# c421.net
KiCad netlist of a schematic drawn in EAGLE
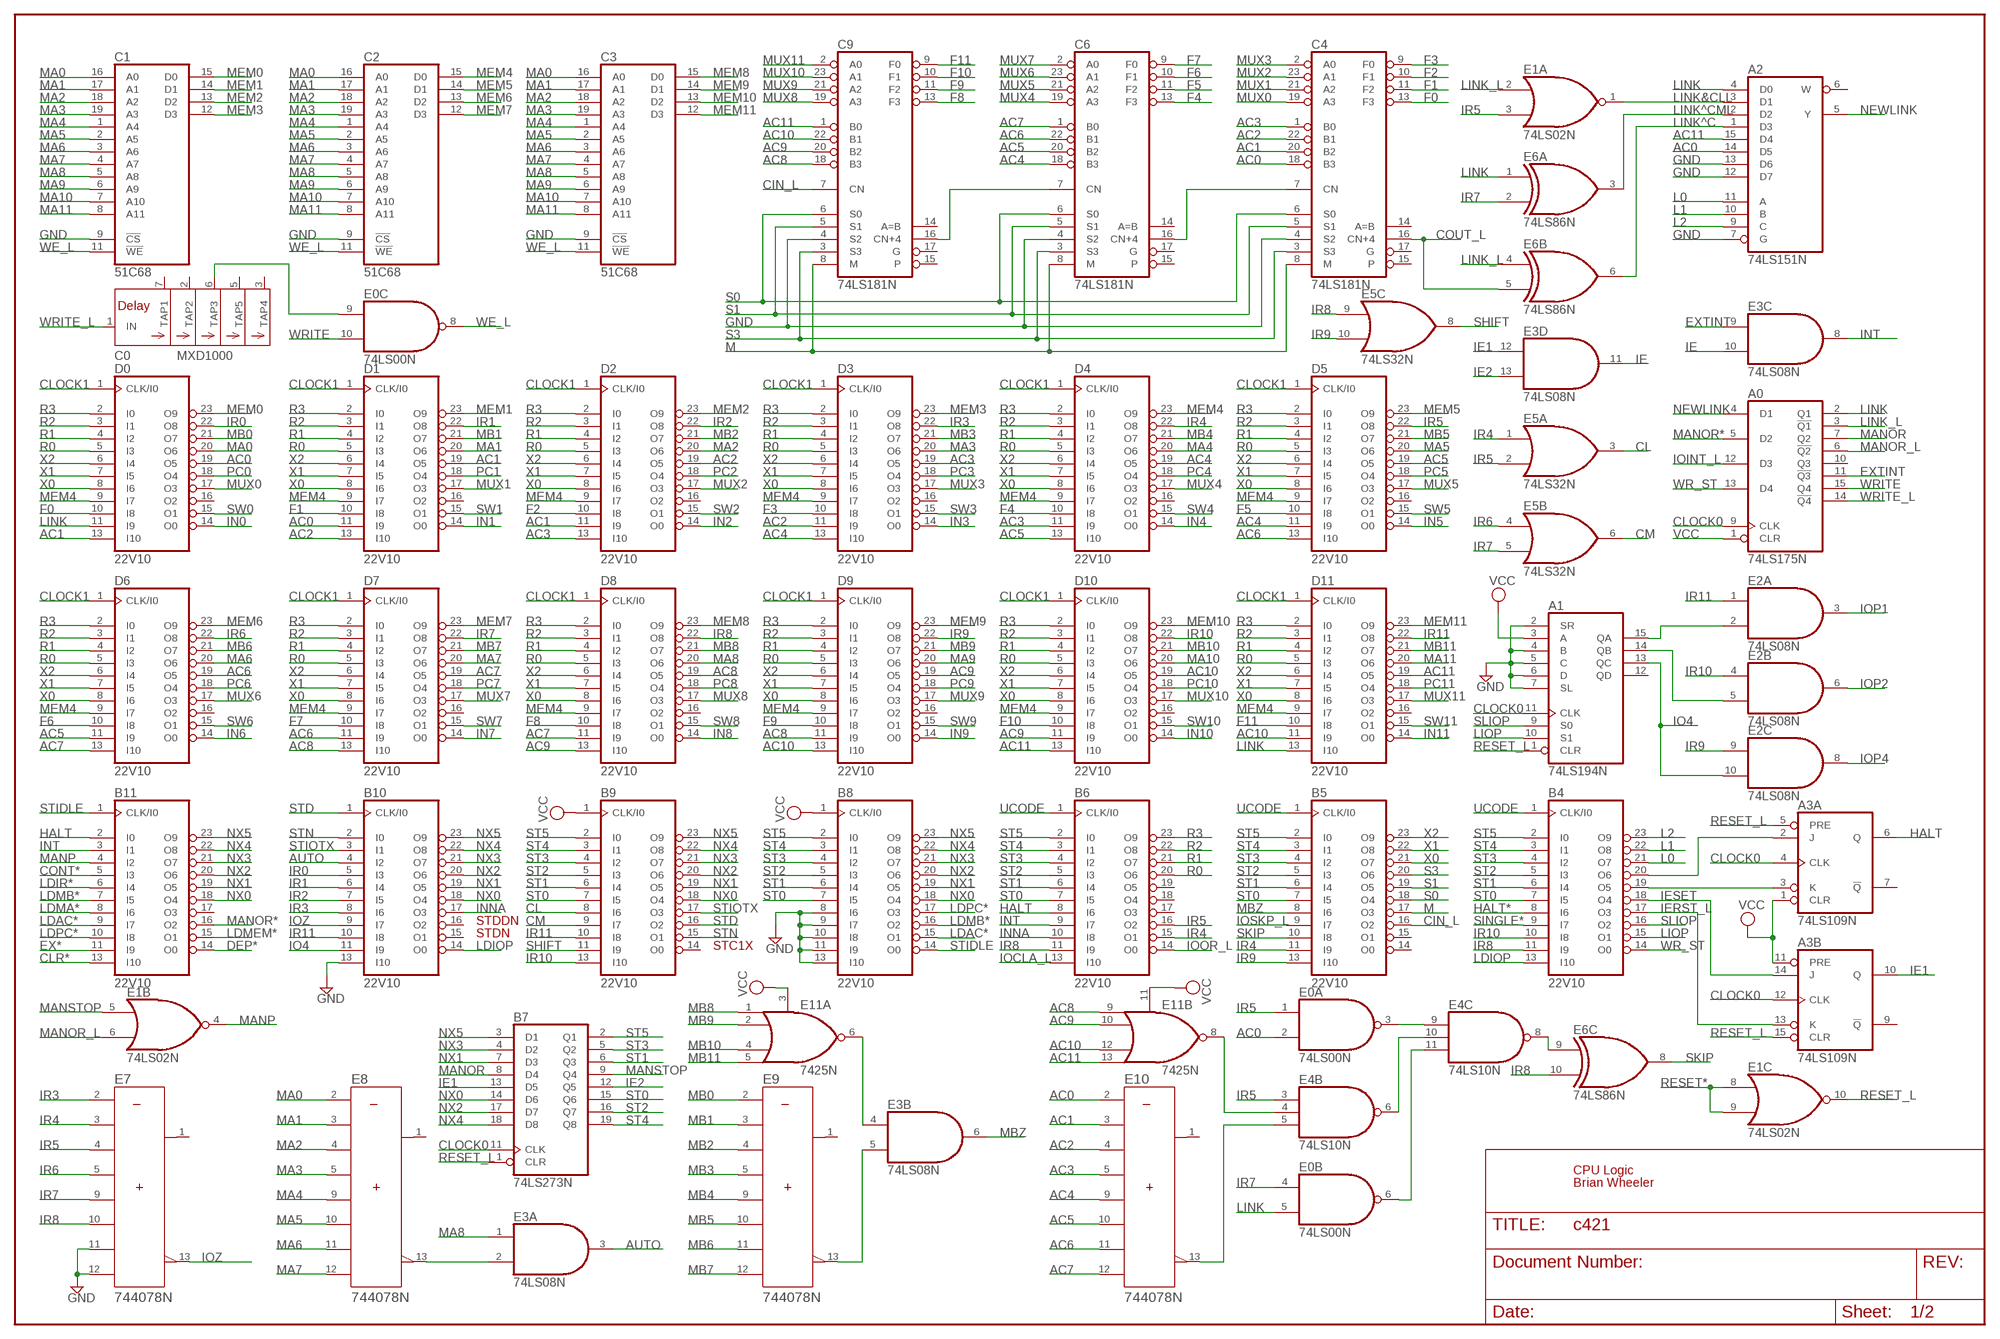
[diagram p0: schematic, sheet 1]
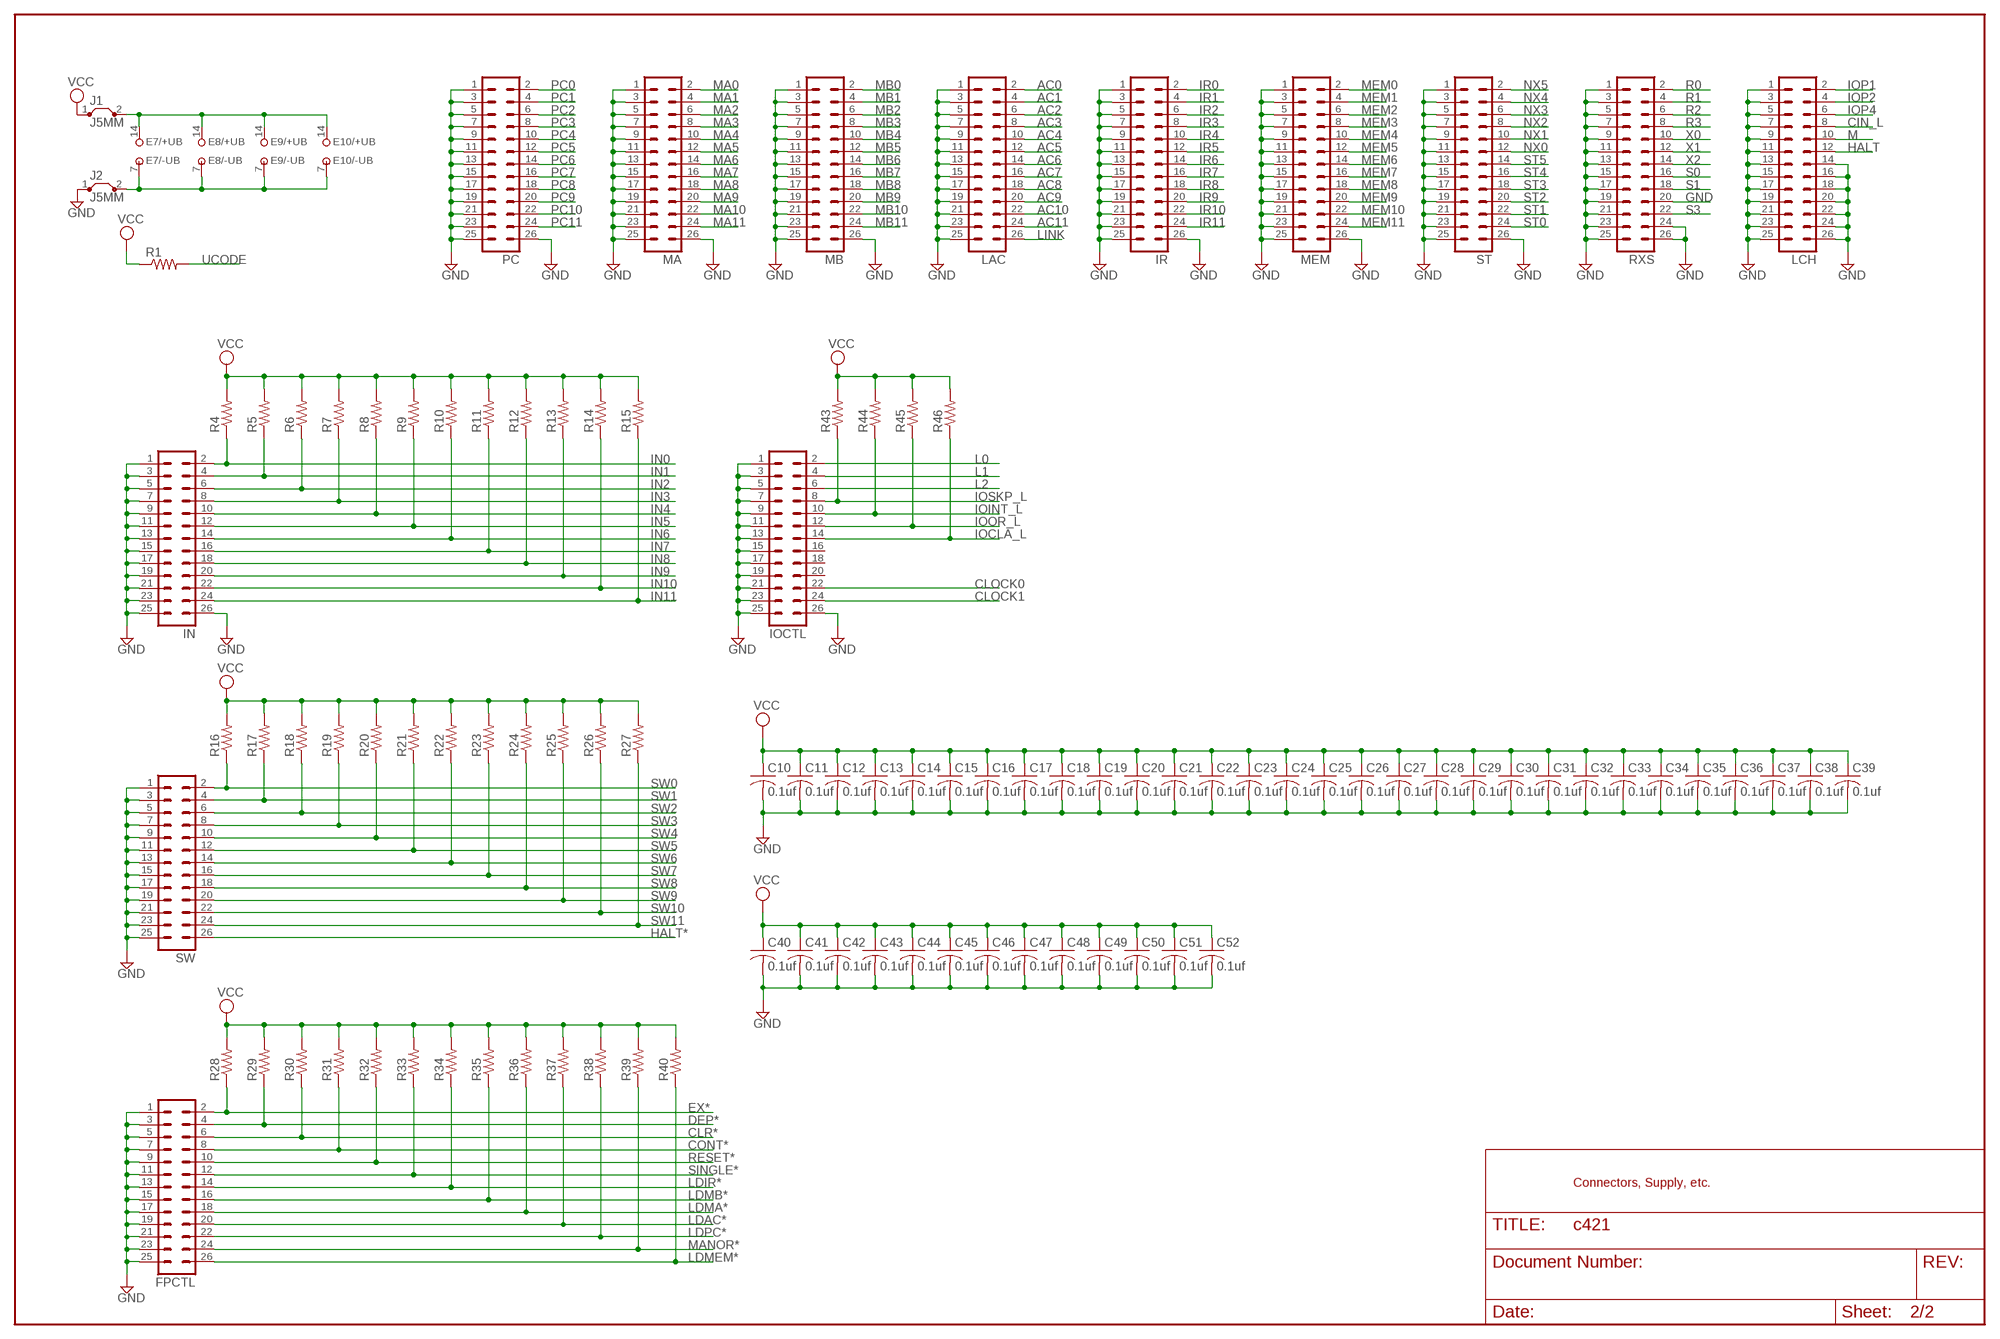
[diagram p1: schematic, sheet 2]

(export (version "E")
  (design (tool "Eeschema 10.0.6"))
  (components
    (comp (ref "A0")
      (value "74LS175N")
      (footprint "eagle-import:DIL16")
      (libsource (lib "eagle-import") (part "74175NLS"))
    )
    (comp (ref "A1")
      (value "74LS194N")
      (footprint "eagle-import:DIL16")
      (libsource (lib "eagle-import") (part "74194NS"))
    )
    (comp (ref "A2")
      (value "74LS151N")
      (footprint "eagle-import:DIL16")
      (libsource (lib "eagle-import") (part "74151NLS"))
    )
    (comp (ref "A3")
      (value "74LS109N")
      (footprint "eagle-import:DIL16")
      (libsource (lib "eagle-import") (part "74109NLS"))
    )
    (comp (ref "B4")
      (value "22V10")
      (footprint "eagle-import:DIL24-3")
      (fields (field (name "MPN") "GAL22V10D-7LPN"))
      (libsource (lib "eagle-import") (part "22V10"))
    )
    (comp (ref "B5")
      (value "22V10")
      (footprint "eagle-import:DIL24-3")
      (fields (field (name "MPN") "GAL22V10D-7LPN"))
      (libsource (lib "eagle-import") (part "22V10"))
    )
    (comp (ref "B6")
      (value "22V10")
      (footprint "eagle-import:DIL24-3")
      (fields (field (name "MPN") "GAL22V10D-7LPN"))
      (libsource (lib "eagle-import") (part "22V10"))
    )
    (comp (ref "B7")
      (value "74LS273N")
      (footprint "eagle-import:DIL20")
      (libsource (lib "eagle-import") (part "74273N"))
    )
    (comp (ref "B8")
      (value "22V10")
      (footprint "eagle-import:DIL24-3")
      (fields (field (name "MPN") "GAL22V10D-7LPN"))
      (libsource (lib "eagle-import") (part "22V10"))
    )
    (comp (ref "B9")
      (value "22V10")
      (footprint "eagle-import:DIL24-3")
      (fields (field (name "MPN") "GAL22V10D-7LPN"))
      (libsource (lib "eagle-import") (part "22V10"))
    )
    (comp (ref "B10")
      (value "22V10")
      (footprint "eagle-import:DIL24-3")
      (fields (field (name "MPN") "GAL22V10D-7LPN"))
      (libsource (lib "eagle-import") (part "22V10"))
    )
    (comp (ref "B11")
      (value "22V10")
      (footprint "eagle-import:DIL24-3")
      (fields (field (name "MPN") "GAL22V10D-7LPN"))
      (libsource (lib "eagle-import") (part "22V10"))
    )
    (comp (ref "C0")
      (value "MXD1000")
      (footprint "eagle-import:DIL08")
      (libsource (lib "eagle-import") (part "MXD1000"))
    )
    (comp (ref "C1")
      (value "51C68")
      (footprint "eagle-import:DIL20")
      (libsource (lib "eagle-import") (part "51C68"))
    )
    (comp (ref "C2")
      (value "51C68")
      (footprint "eagle-import:DIL20")
      (libsource (lib "eagle-import") (part "51C68"))
    )
    (comp (ref "C3")
      (value "51C68")
      (footprint "eagle-import:DIL20")
      (libsource (lib "eagle-import") (part "51C68"))
    )
    (comp (ref "C4")
      (value "74LS181N")
      (footprint "eagle-import:DIL24-6")
      (libsource (lib "eagle-import") (part "74181NLS"))
    )
    (comp (ref "C6")
      (value "74LS181N")
      (footprint "eagle-import:DIL24-6")
      (libsource (lib "eagle-import") (part "74181NLS"))
    )
    (comp (ref "C9")
      (value "74LS181N")
      (footprint "eagle-import:DIL24-6")
      (libsource (lib "eagle-import") (part "74181NLS"))
    )
    (comp (ref "D0")
      (value "22V10")
      (footprint "eagle-import:DIL24-3")
      (fields (field (name "MPN") "GAL22V10D-7LPN"))
      (libsource (lib "eagle-import") (part "22V10"))
    )
    (comp (ref "D1")
      (value "22V10")
      (footprint "eagle-import:DIL24-3")
      (fields (field (name "MPN") "GAL22V10D-7LPN"))
      (libsource (lib "eagle-import") (part "22V10"))
    )
    (comp (ref "D2")
      (value "22V10")
      (footprint "eagle-import:DIL24-3")
      (fields (field (name "MPN") "GAL22V10D-7LPN"))
      (libsource (lib "eagle-import") (part "22V10"))
    )
    (comp (ref "D3")
      (value "22V10")
      (footprint "eagle-import:DIL24-3")
      (fields (field (name "MPN") "GAL22V10D-7LPN"))
      (libsource (lib "eagle-import") (part "22V10"))
    )
    (comp (ref "D4")
      (value "22V10")
      (footprint "eagle-import:DIL24-3")
      (fields (field (name "MPN") "GAL22V10D-7LPN"))
      (libsource (lib "eagle-import") (part "22V10"))
    )
    (comp (ref "D5")
      (value "22V10")
      (footprint "eagle-import:DIL24-3")
      (fields (field (name "MPN") "GAL22V10D-7LPN"))
      (libsource (lib "eagle-import") (part "22V10"))
    )
    (comp (ref "D6")
      (value "22V10")
      (footprint "eagle-import:DIL24-3")
      (fields (field (name "MPN") "GAL22V10D-7LPN"))
      (libsource (lib "eagle-import") (part "22V10"))
    )
    (comp (ref "D7")
      (value "22V10")
      (footprint "eagle-import:DIL24-3")
      (fields (field (name "MPN") "GAL22V10D-7LPN"))
      (libsource (lib "eagle-import") (part "22V10"))
    )
    (comp (ref "D8")
      (value "22V10")
      (footprint "eagle-import:DIL24-3")
      (fields (field (name "MPN") "GAL22V10D-7LPN"))
      (libsource (lib "eagle-import") (part "22V10"))
    )
    (comp (ref "D9")
      (value "22V10")
      (footprint "eagle-import:DIL24-3")
      (fields (field (name "MPN") "GAL22V10D-7LPN"))
      (libsource (lib "eagle-import") (part "22V10"))
    )
    (comp (ref "D10")
      (value "22V10")
      (footprint "eagle-import:DIL24-3")
      (fields (field (name "MPN") "GAL22V10D-7LPN"))
      (libsource (lib "eagle-import") (part "22V10"))
    )
    (comp (ref "D11")
      (value "22V10")
      (footprint "eagle-import:DIL24-3")
      (fields (field (name "MPN") "GAL22V10D-7LPN"))
      (libsource (lib "eagle-import") (part "22V10"))
    )
    (comp (ref "E0")
      (value "74LS00N")
      (footprint "eagle-import:DIL14")
      (libsource (lib "eagle-import") (part "7400NLS"))
    )
    (comp (ref "E1")
      (value "74LS02N")
      (footprint "eagle-import:DIL14")
      (libsource (lib "eagle-import") (part "7402NLS"))
    )
    (comp (ref "E2")
      (value "74LS08N")
      (footprint "eagle-import:DIL14")
      (libsource (lib "eagle-import") (part "7408NLS"))
    )
    (comp (ref "E3")
      (value "74LS08N")
      (footprint "eagle-import:DIL14")
      (libsource (lib "eagle-import") (part "7408NLS"))
    )
    (comp (ref "E4")
      (value "74LS10N")
      (footprint "eagle-import:DIL14")
      (libsource (lib "eagle-import") (part "7410NLS"))
    )
    (comp (ref "E5")
      (value "74LS32N")
      (footprint "eagle-import:DIL14")
      (libsource (lib "eagle-import") (part "7432NLS"))
    )
    (comp (ref "E6")
      (value "74LS86N")
      (footprint "eagle-import:DIL14")
      (libsource (lib "eagle-import") (part "7486NLS"))
    )
    (comp (ref "E7")
      (value "744078N")
      (footprint "eagle-import:DIL14")
      (libsource (lib "eagle-import") (part "744078N"))
    )
    (comp (ref "E8")
      (value "744078N")
      (footprint "eagle-import:DIL14")
      (libsource (lib "eagle-import") (part "744078N"))
    )
    (comp (ref "E9")
      (value "744078N")
      (footprint "eagle-import:DIL14")
      (libsource (lib "eagle-import") (part "744078N"))
    )
    (comp (ref "E10")
      (value "744078N")
      (footprint "eagle-import:DIL14")
      (libsource (lib "eagle-import") (part "744078N"))
    )
    (comp (ref "E11")
      (value "7425N")
      (footprint "eagle-import:DIL14")
      (libsource (lib "eagle-import") (part "7425N"))
    )
    (comp (ref "C10")
      (value "0.1uf")
      (footprint "eagle-import:C050-025X075")
      (libsource (lib "eagle-import") (part "C-US050-025X075"))
    )
    (comp (ref "C11")
      (value "0.1uf")
      (footprint "eagle-import:C050-025X075")
      (libsource (lib "eagle-import") (part "C-US050-025X075"))
    )
    (comp (ref "C12")
      (value "0.1uf")
      (footprint "eagle-import:C050-025X075")
      (libsource (lib "eagle-import") (part "C-US050-025X075"))
    )
    (comp (ref "C13")
      (value "0.1uf")
      (footprint "eagle-import:C050-025X075")
      (libsource (lib "eagle-import") (part "C-US050-025X075"))
    )
    (comp (ref "C14")
      (value "0.1uf")
      (footprint "eagle-import:C050-025X075")
      (libsource (lib "eagle-import") (part "C-US050-025X075"))
    )
    (comp (ref "C15")
      (value "0.1uf")
      (footprint "eagle-import:C050-025X075")
      (libsource (lib "eagle-import") (part "C-US050-025X075"))
    )
    (comp (ref "C16")
      (value "0.1uf")
      (footprint "eagle-import:C050-025X075")
      (libsource (lib "eagle-import") (part "C-US050-025X075"))
    )
    (comp (ref "C17")
      (value "0.1uf")
      (footprint "eagle-import:C050-025X075")
      (libsource (lib "eagle-import") (part "C-US050-025X075"))
    )
    (comp (ref "C18")
      (value "0.1uf")
      (footprint "eagle-import:C050-025X075")
      (libsource (lib "eagle-import") (part "C-US050-025X075"))
    )
    (comp (ref "C19")
      (value "0.1uf")
      (footprint "eagle-import:C050-025X075")
      (libsource (lib "eagle-import") (part "C-US050-025X075"))
    )
    (comp (ref "C20")
      (value "0.1uf")
      (footprint "eagle-import:C050-025X075")
      (libsource (lib "eagle-import") (part "C-US050-025X075"))
    )
    (comp (ref "C21")
      (value "0.1uf")
      (footprint "eagle-import:C050-025X075")
      (libsource (lib "eagle-import") (part "C-US050-025X075"))
    )
    (comp (ref "C22")
      (value "0.1uf")
      (footprint "eagle-import:C050-025X075")
      (libsource (lib "eagle-import") (part "C-US050-025X075"))
    )
    (comp (ref "C23")
      (value "0.1uf")
      (footprint "eagle-import:C050-025X075")
      (libsource (lib "eagle-import") (part "C-US050-025X075"))
    )
    (comp (ref "C24")
      (value "0.1uf")
      (footprint "eagle-import:C050-025X075")
      (libsource (lib "eagle-import") (part "C-US050-025X075"))
    )
    (comp (ref "C25")
      (value "0.1uf")
      (footprint "eagle-import:C050-025X075")
      (libsource (lib "eagle-import") (part "C-US050-025X075"))
    )
    (comp (ref "C26")
      (value "0.1uf")
      (footprint "eagle-import:C050-025X075")
      (libsource (lib "eagle-import") (part "C-US050-025X075"))
    )
    (comp (ref "C27")
      (value "0.1uf")
      (footprint "eagle-import:C050-025X075")
      (libsource (lib "eagle-import") (part "C-US050-025X075"))
    )
    (comp (ref "C28")
      (value "0.1uf")
      (footprint "eagle-import:C050-025X075")
      (libsource (lib "eagle-import") (part "C-US050-025X075"))
    )
    (comp (ref "C29")
      (value "0.1uf")
      (footprint "eagle-import:C050-025X075")
      (libsource (lib "eagle-import") (part "C-US050-025X075"))
    )
    (comp (ref "C30")
      (value "0.1uf")
      (footprint "eagle-import:C050-025X075")
      (libsource (lib "eagle-import") (part "C-US050-025X075"))
    )
    (comp (ref "C31")
      (value "0.1uf")
      (footprint "eagle-import:C050-025X075")
      (libsource (lib "eagle-import") (part "C-US050-025X075"))
    )
    (comp (ref "C32")
      (value "0.1uf")
      (footprint "eagle-import:C050-025X075")
      (libsource (lib "eagle-import") (part "C-US050-025X075"))
    )
    (comp (ref "C33")
      (value "0.1uf")
      (footprint "eagle-import:C050-025X075")
      (libsource (lib "eagle-import") (part "C-US050-025X075"))
    )
    (comp (ref "C34")
      (value "0.1uf")
      (footprint "eagle-import:C050-025X075")
      (libsource (lib "eagle-import") (part "C-US050-025X075"))
    )
    (comp (ref "C35")
      (value "0.1uf")
      (footprint "eagle-import:C050-025X075")
      (libsource (lib "eagle-import") (part "C-US050-025X075"))
    )
    (comp (ref "C36")
      (value "0.1uf")
      (footprint "eagle-import:C050-025X075")
      (libsource (lib "eagle-import") (part "C-US050-025X075"))
    )
    (comp (ref "C37")
      (value "0.1uf")
      (footprint "eagle-import:C050-025X075")
      (libsource (lib "eagle-import") (part "C-US050-025X075"))
    )
    (comp (ref "C38")
      (value "0.1uf")
      (footprint "eagle-import:C050-025X075")
      (libsource (lib "eagle-import") (part "C-US050-025X075"))
    )
    (comp (ref "C39")
      (value "0.1uf")
      (footprint "eagle-import:C050-025X075")
      (libsource (lib "eagle-import") (part "C-US050-025X075"))
    )
    (comp (ref "C40")
      (value "0.1uf")
      (footprint "eagle-import:C050-025X075")
      (libsource (lib "eagle-import") (part "C-US050-025X075"))
    )
    (comp (ref "C41")
      (value "0.1uf")
      (footprint "eagle-import:C050-025X075")
      (libsource (lib "eagle-import") (part "C-US050-025X075"))
    )
    (comp (ref "C42")
      (value "0.1uf")
      (footprint "eagle-import:C050-025X075")
      (libsource (lib "eagle-import") (part "C-US050-025X075"))
    )
    (comp (ref "C43")
      (value "0.1uf")
      (footprint "eagle-import:C050-025X075")
      (libsource (lib "eagle-import") (part "C-US050-025X075"))
    )
    (comp (ref "C44")
      (value "0.1uf")
      (footprint "eagle-import:C050-025X075")
      (libsource (lib "eagle-import") (part "C-US050-025X075"))
    )
    (comp (ref "C45")
      (value "0.1uf")
      (footprint "eagle-import:C050-025X075")
      (libsource (lib "eagle-import") (part "C-US050-025X075"))
    )
    (comp (ref "C46")
      (value "0.1uf")
      (footprint "eagle-import:C050-025X075")
      (libsource (lib "eagle-import") (part "C-US050-025X075"))
    )
    (comp (ref "C47")
      (value "0.1uf")
      (footprint "eagle-import:C050-025X075")
      (libsource (lib "eagle-import") (part "C-US050-025X075"))
    )
    (comp (ref "C48")
      (value "0.1uf")
      (footprint "eagle-import:C050-025X075")
      (libsource (lib "eagle-import") (part "C-US050-025X075"))
    )
    (comp (ref "C49")
      (value "0.1uf")
      (footprint "eagle-import:C050-025X075")
      (libsource (lib "eagle-import") (part "C-US050-025X075"))
    )
    (comp (ref "C50")
      (value "0.1uf")
      (footprint "eagle-import:C050-025X075")
      (libsource (lib "eagle-import") (part "C-US050-025X075"))
    )
    (comp (ref "C51")
      (value "0.1uf")
      (footprint "eagle-import:C050-025X075")
      (libsource (lib "eagle-import") (part "C-US050-025X075"))
    )
    (comp (ref "C52")
      (value "0.1uf")
      (footprint "eagle-import:C050-025X075")
      (libsource (lib "eagle-import") (part "C-US050-025X075"))
    )
    (comp (ref "FPCTL")
      (value "ML26")
      (footprint "eagle-import:ML26")
      (libsource (lib "eagle-import") (part "ML26"))
    )
    (comp (ref "IN")
      (value "ML26")
      (footprint "eagle-import:ML26")
      (libsource (lib "eagle-import") (part "ML26"))
    )
    (comp (ref "IOCTL")
      (value "ML26")
      (footprint "eagle-import:ML26")
      (libsource (lib "eagle-import") (part "ML26"))
    )
    (comp (ref "IR")
      (value "ML26")
      (footprint "eagle-import:ML26")
      (libsource (lib "eagle-import") (part "ML26"))
    )
    (comp (ref "J1")
      (value "J5MM")
      (footprint "eagle-import:05")
      (libsource (lib "eagle-import") (part "J5MM"))
    )
    (comp (ref "J2")
      (value "J5MM")
      (footprint "eagle-import:05")
      (libsource (lib "eagle-import") (part "J5MM"))
    )
    (comp (ref "LAC")
      (value "ML26")
      (footprint "eagle-import:ML26")
      (libsource (lib "eagle-import") (part "ML26"))
    )
    (comp (ref "LCH")
      (value "ML26")
      (footprint "eagle-import:ML26")
      (libsource (lib "eagle-import") (part "ML26"))
    )
    (comp (ref "MA")
      (value "ML26")
      (footprint "eagle-import:ML26")
      (libsource (lib "eagle-import") (part "ML26"))
    )
    (comp (ref "MB")
      (value "ML26")
      (footprint "eagle-import:ML26")
      (libsource (lib "eagle-import") (part "ML26"))
    )
    (comp (ref "MEM")
      (value "ML26")
      (footprint "eagle-import:ML26")
      (libsource (lib "eagle-import") (part "ML26"))
    )
    (comp (ref "PC")
      (value "ML26")
      (footprint "eagle-import:ML26")
      (libsource (lib "eagle-import") (part "ML26"))
    )
    (comp (ref "R1")
      (value "R-US_0207/10")
      (footprint "eagle-import:0207_10")
      (libsource (lib "eagle-import") (part "R-US_0207/10"))
    )
    (comp (ref "R4")
      (value "R-US_0207/10")
      (footprint "eagle-import:0207_10")
      (libsource (lib "eagle-import") (part "R-US_0207/10"))
    )
    (comp (ref "R5")
      (value "R-US_0207/10")
      (footprint "eagle-import:0207_10")
      (libsource (lib "eagle-import") (part "R-US_0207/10"))
    )
    (comp (ref "R6")
      (value "R-US_0207/10")
      (footprint "eagle-import:0207_10")
      (libsource (lib "eagle-import") (part "R-US_0207/10"))
    )
    (comp (ref "R7")
      (value "R-US_0207/10")
      (footprint "eagle-import:0207_10")
      (libsource (lib "eagle-import") (part "R-US_0207/10"))
    )
    (comp (ref "R8")
      (value "R-US_0207/10")
      (footprint "eagle-import:0207_10")
      (libsource (lib "eagle-import") (part "R-US_0207/10"))
    )
    (comp (ref "R9")
      (value "R-US_0207/10")
      (footprint "eagle-import:0207_10")
      (libsource (lib "eagle-import") (part "R-US_0207/10"))
    )
    (comp (ref "R10")
      (value "R-US_0207/10")
      (footprint "eagle-import:0207_10")
      (libsource (lib "eagle-import") (part "R-US_0207/10"))
    )
    (comp (ref "R11")
      (value "R-US_0207/10")
      (footprint "eagle-import:0207_10")
      (libsource (lib "eagle-import") (part "R-US_0207/10"))
    )
    (comp (ref "R12")
      (value "R-US_0207/10")
      (footprint "eagle-import:0207_10")
      (libsource (lib "eagle-import") (part "R-US_0207/10"))
    )
    (comp (ref "R13")
      (value "R-US_0207/10")
      (footprint "eagle-import:0207_10")
      (libsource (lib "eagle-import") (part "R-US_0207/10"))
    )
    (comp (ref "R14")
      (value "R-US_0207/10")
      (footprint "eagle-import:0207_10")
      (libsource (lib "eagle-import") (part "R-US_0207/10"))
    )
    (comp (ref "R15")
      (value "R-US_0207/10")
      (footprint "eagle-import:0207_10")
      (libsource (lib "eagle-import") (part "R-US_0207/10"))
    )
    (comp (ref "R16")
      (value "R-US_0207/10")
      (footprint "eagle-import:0207_10")
      (libsource (lib "eagle-import") (part "R-US_0207/10"))
    )
    (comp (ref "R17")
      (value "R-US_0207/10")
      (footprint "eagle-import:0207_10")
      (libsource (lib "eagle-import") (part "R-US_0207/10"))
    )
    (comp (ref "R18")
      (value "R-US_0207/10")
      (footprint "eagle-import:0207_10")
      (libsource (lib "eagle-import") (part "R-US_0207/10"))
    )
    (comp (ref "R19")
      (value "R-US_0207/10")
      (footprint "eagle-import:0207_10")
      (libsource (lib "eagle-import") (part "R-US_0207/10"))
    )
    (comp (ref "R20")
      (value "R-US_0207/10")
      (footprint "eagle-import:0207_10")
      (libsource (lib "eagle-import") (part "R-US_0207/10"))
    )
    (comp (ref "R21")
      (value "R-US_0207/10")
      (footprint "eagle-import:0207_10")
      (libsource (lib "eagle-import") (part "R-US_0207/10"))
    )
    (comp (ref "R22")
      (value "R-US_0207/10")
      (footprint "eagle-import:0207_10")
      (libsource (lib "eagle-import") (part "R-US_0207/10"))
    )
    (comp (ref "R23")
      (value "R-US_0207/10")
      (footprint "eagle-import:0207_10")
      (libsource (lib "eagle-import") (part "R-US_0207/10"))
    )
    (comp (ref "R24")
      (value "R-US_0207/10")
      (footprint "eagle-import:0207_10")
      (libsource (lib "eagle-import") (part "R-US_0207/10"))
    )
    (comp (ref "R25")
      (value "R-US_0207/10")
      (footprint "eagle-import:0207_10")
      (libsource (lib "eagle-import") (part "R-US_0207/10"))
    )
    (comp (ref "R26")
      (value "R-US_0207/10")
      (footprint "eagle-import:0207_10")
      (libsource (lib "eagle-import") (part "R-US_0207/10"))
    )
    (comp (ref "R27")
      (value "R-US_0207/10")
      (footprint "eagle-import:0207_10")
      (libsource (lib "eagle-import") (part "R-US_0207/10"))
    )
    (comp (ref "R28")
      (value "R-US_0207/10")
      (footprint "eagle-import:0207_10")
      (libsource (lib "eagle-import") (part "R-US_0207/10"))
    )
    (comp (ref "R29")
      (value "R-US_0207/10")
      (footprint "eagle-import:0207_10")
      (libsource (lib "eagle-import") (part "R-US_0207/10"))
    )
    (comp (ref "R30")
      (value "R-US_0207/10")
      (footprint "eagle-import:0207_10")
      (libsource (lib "eagle-import") (part "R-US_0207/10"))
    )
    (comp (ref "R31")
      (value "R-US_0207/10")
      (footprint "eagle-import:0207_10")
      (libsource (lib "eagle-import") (part "R-US_0207/10"))
    )
    (comp (ref "R32")
      (value "R-US_0207/10")
      (footprint "eagle-import:0207_10")
      (libsource (lib "eagle-import") (part "R-US_0207/10"))
    )
    (comp (ref "R33")
      (value "R-US_0207/10")
      (footprint "eagle-import:0207_10")
      (libsource (lib "eagle-import") (part "R-US_0207/10"))
    )
    (comp (ref "R34")
      (value "R-US_0207/10")
      (footprint "eagle-import:0207_10")
      (libsource (lib "eagle-import") (part "R-US_0207/10"))
    )
    (comp (ref "R35")
      (value "R-US_0207/10")
      (footprint "eagle-import:0207_10")
      (libsource (lib "eagle-import") (part "R-US_0207/10"))
    )
    (comp (ref "R36")
      (value "R-US_0207/10")
      (footprint "eagle-import:0207_10")
      (libsource (lib "eagle-import") (part "R-US_0207/10"))
    )
    (comp (ref "R37")
      (value "R-US_0207/10")
      (footprint "eagle-import:0207_10")
      (libsource (lib "eagle-import") (part "R-US_0207/10"))
    )
    (comp (ref "R38")
      (value "R-US_0207/10")
      (footprint "eagle-import:0207_10")
      (libsource (lib "eagle-import") (part "R-US_0207/10"))
    )
    (comp (ref "R39")
      (value "R-US_0207/10")
      (footprint "eagle-import:0207_10")
      (libsource (lib "eagle-import") (part "R-US_0207/10"))
    )
    (comp (ref "R40")
      (value "R-US_0207/10")
      (footprint "eagle-import:0207_10")
      (libsource (lib "eagle-import") (part "R-US_0207/10"))
    )
    (comp (ref "R43")
      (value "R-US_0207/10")
      (footprint "eagle-import:0207_10")
      (libsource (lib "eagle-import") (part "R-US_0207/10"))
    )
    (comp (ref "R44")
      (value "R-US_0207/10")
      (footprint "eagle-import:0207_10")
      (libsource (lib "eagle-import") (part "R-US_0207/10"))
    )
    (comp (ref "R45")
      (value "R-US_0207/10")
      (footprint "eagle-import:0207_10")
      (libsource (lib "eagle-import") (part "R-US_0207/10"))
    )
    (comp (ref "R46")
      (value "R-US_0207/10")
      (footprint "eagle-import:0207_10")
      (libsource (lib "eagle-import") (part "R-US_0207/10"))
    )
    (comp (ref "RXS")
      (value "ML26")
      (footprint "eagle-import:ML26")
      (libsource (lib "eagle-import") (part "ML26"))
    )
    (comp (ref "ST")
      (value "ML26")
      (footprint "eagle-import:ML26")
      (libsource (lib "eagle-import") (part "ML26"))
    )
    (comp (ref "SW")
      (value "ML26")
      (footprint "eagle-import:ML26")
      (libsource (lib "eagle-import") (part "ML26"))
    )
  )
  (nets
    (net (code "1") (name "AC0") (class "Default")
      (node (ref "A2") (pin "14") (pinfunction "D5_14") (pintype "input"))
      (node (ref "C4") (pin "18") (pinfunction "B3_18") (pintype "input"))
      (node (ref "D0") (pin "19") (pinfunction "O5_19") (pintype "bidirectional"))
      (node (ref "D1") (pin "11") (pinfunction "I9_11") (pintype "input"))
      (node (ref "E0") (pin "2") (pinfunction "I1_2") (pintype "input"))
      (node (ref "E10") (pin "2") (pinfunction "A_2") (pintype "input"))
      (node (ref "LAC") (pin "2") (pinfunction "2_2") (pintype "passive"))
    )
    (net (code "2") (name "AC1") (class "Default")
      (node (ref "C4") (pin "20") (pinfunction "B2_20") (pintype "input"))
      (node (ref "D0") (pin "13") (pinfunction "I10_13") (pintype "input"))
      (node (ref "D1") (pin "19") (pinfunction "O5_19") (pintype "bidirectional"))
      (node (ref "D2") (pin "11") (pinfunction "I9_11") (pintype "input"))
      (node (ref "E10") (pin "3") (pinfunction "B_3") (pintype "input"))
      (node (ref "LAC") (pin "4") (pinfunction "4_4") (pintype "passive"))
    )
    (net (code "3") (name "AC2") (class "Default")
      (node (ref "C4") (pin "22") (pinfunction "B1_22") (pintype "input"))
      (node (ref "D1") (pin "13") (pinfunction "I10_13") (pintype "input"))
      (node (ref "D2") (pin "19") (pinfunction "O5_19") (pintype "bidirectional"))
      (node (ref "D3") (pin "11") (pinfunction "I9_11") (pintype "input"))
      (node (ref "E10") (pin "4") (pinfunction "C_4") (pintype "input"))
      (node (ref "LAC") (pin "6") (pinfunction "6_6") (pintype "passive"))
    )
    (net (code "4") (name "AC3") (class "Default")
      (node (ref "C4") (pin "1") (pinfunction "B0_1") (pintype "input"))
      (node (ref "D2") (pin "13") (pinfunction "I10_13") (pintype "input"))
      (node (ref "D3") (pin "19") (pinfunction "O5_19") (pintype "bidirectional"))
      (node (ref "D4") (pin "11") (pinfunction "I9_11") (pintype "input"))
      (node (ref "E10") (pin "5") (pinfunction "D_5") (pintype "input"))
      (node (ref "LAC") (pin "8") (pinfunction "8_8") (pintype "passive"))
    )
    (net (code "5") (name "AC4") (class "Default")
      (node (ref "C6") (pin "18") (pinfunction "B3_18") (pintype "input"))
      (node (ref "D3") (pin "13") (pinfunction "I10_13") (pintype "input"))
      (node (ref "D4") (pin "19") (pinfunction "O5_19") (pintype "bidirectional"))
      (node (ref "D5") (pin "11") (pinfunction "I9_11") (pintype "input"))
      (node (ref "E10") (pin "9") (pinfunction "E_9") (pintype "input"))
      (node (ref "LAC") (pin "10") (pinfunction "10_10") (pintype "passive"))
    )
    (net (code "6") (name "AC5") (class "Default")
      (node (ref "C6") (pin "20") (pinfunction "B2_20") (pintype "input"))
      (node (ref "D4") (pin "13") (pinfunction "I10_13") (pintype "input"))
      (node (ref "D5") (pin "19") (pinfunction "O5_19") (pintype "bidirectional"))
      (node (ref "D6") (pin "11") (pinfunction "I9_11") (pintype "input"))
      (node (ref "E10") (pin "10") (pinfunction "F_10") (pintype "input"))
      (node (ref "LAC") (pin "12") (pinfunction "12_12") (pintype "passive"))
    )
    (net (code "7") (name "AC6") (class "Default")
      (node (ref "C6") (pin "22") (pinfunction "B1_22") (pintype "input"))
      (node (ref "D5") (pin "13") (pinfunction "I10_13") (pintype "input"))
      (node (ref "D6") (pin "19") (pinfunction "O5_19") (pintype "bidirectional"))
      (node (ref "D7") (pin "11") (pinfunction "I9_11") (pintype "input"))
      (node (ref "E10") (pin "11") (pinfunction "G_11") (pintype "input"))
      (node (ref "LAC") (pin "14") (pinfunction "14_14") (pintype "passive"))
    )
    (net (code "8") (name "AC7") (class "Default")
      (node (ref "C6") (pin "1") (pinfunction "B0_1") (pintype "input"))
      (node (ref "D6") (pin "13") (pinfunction "I10_13") (pintype "input"))
      (node (ref "D7") (pin "19") (pinfunction "O5_19") (pintype "bidirectional"))
      (node (ref "D8") (pin "11") (pinfunction "I9_11") (pintype "input"))
      (node (ref "E10") (pin "12") (pinfunction "H_12") (pintype "input"))
      (node (ref "LAC") (pin "16") (pinfunction "16_16") (pintype "passive"))
    )
    (net (code "9") (name "AC8") (class "Default")
      (node (ref "C9") (pin "18") (pinfunction "B3_18") (pintype "input"))
      (node (ref "D7") (pin "13") (pinfunction "I10_13") (pintype "input"))
      (node (ref "D8") (pin "19") (pinfunction "O5_19") (pintype "bidirectional"))
      (node (ref "D9") (pin "11") (pinfunction "I9_11") (pintype "input"))
      (node (ref "E11") (pin "9") (pinfunction "I0_9") (pintype "input"))
      (node (ref "LAC") (pin "18") (pinfunction "18_18") (pintype "passive"))
    )
    (net (code "10") (name "AC9") (class "Default")
      (node (ref "C9") (pin "20") (pinfunction "B2_20") (pintype "input"))
      (node (ref "D10") (pin "11") (pinfunction "I9_11") (pintype "input"))
      (node (ref "D8") (pin "13") (pinfunction "I10_13") (pintype "input"))
      (node (ref "D9") (pin "19") (pinfunction "O5_19") (pintype "bidirectional"))
      (node (ref "E11") (pin "10") (pinfunction "I1_10") (pintype "input"))
      (node (ref "LAC") (pin "20") (pinfunction "20_20") (pintype "passive"))
    )
    (net (code "11") (name "AC10") (class "Default")
      (node (ref "C9") (pin "22") (pinfunction "B1_22") (pintype "input"))
      (node (ref "D10") (pin "19") (pinfunction "O5_19") (pintype "bidirectional"))
      (node (ref "D11") (pin "11") (pinfunction "I9_11") (pintype "input"))
      (node (ref "D9") (pin "13") (pinfunction "I10_13") (pintype "input"))
      (node (ref "E11") (pin "12") (pinfunction "I2_12") (pintype "input"))
      (node (ref "LAC") (pin "22") (pinfunction "22_22") (pintype "passive"))
    )
    (net (code "12") (name "AC11") (class "Default")
      (node (ref "A2") (pin "15") (pinfunction "D4_15") (pintype "input"))
      (node (ref "C9") (pin "1") (pinfunction "B0_1") (pintype "input"))
      (node (ref "D10") (pin "13") (pinfunction "I10_13") (pintype "input"))
      (node (ref "D11") (pin "19") (pinfunction "O5_19") (pintype "bidirectional"))
      (node (ref "E11") (pin "13") (pinfunction "I3_13") (pintype "input"))
      (node (ref "LAC") (pin "24") (pinfunction "24_24") (pintype "passive"))
    )
    (net (code "13") (name "AUTO") (class "Default")
      (node (ref "B10") (pin "4") (pinfunction "I2_4") (pintype "input"))
      (node (ref "E3") (pin "3") (pinfunction "O_3") (pintype "output"))
    )
    (net (code "14") (name "CIN_L") (class "Default")
      (node (ref "B5") (pin "16") (pinfunction "O2_16") (pintype "bidirectional"))
      (node (ref "C9") (pin "7") (pinfunction "CN_7") (pintype "input"))
      (node (ref "LCH") (pin "8") (pinfunction "8_8") (pintype "passive"))
    )
    (net (code "15") (name "CL") (class "Default")
      (node (ref "B9") (pin "8") (pinfunction "I6_8") (pintype "input"))
      (node (ref "E5") (pin "3") (pinfunction "O_3") (pintype "output"))
    )
    (net (code "16") (name "CLOCK0") (class "Default")
      (node (ref "A0") (pin "9") (pinfunction "CLK_9") (pintype "input"))
      (node (ref "A1") (pin "11") (pinfunction "CLK_11") (pintype "input"))
      (node (ref "A3") (pin "12") (pinfunction "CLK_12") (pintype "input"))
      (node (ref "A3") (pin "4") (pinfunction "CLK_4") (pintype "input"))
      (node (ref "B7") (pin "11") (pinfunction "CLK_11") (pintype "input"))
      (node (ref "IOCTL") (pin "22") (pinfunction "22_22") (pintype "passive"))
    )
    (net (code "17") (name "CLOCK1") (class "Default")
      (node (ref "D0") (pin "1") (pinfunction "CLK/I0_1") (pintype "input"))
      (node (ref "D1") (pin "1") (pinfunction "CLK/I0_1") (pintype "input"))
      (node (ref "D10") (pin "1") (pinfunction "CLK/I0_1") (pintype "input"))
      (node (ref "D11") (pin "1") (pinfunction "CLK/I0_1") (pintype "input"))
      (node (ref "D2") (pin "1") (pinfunction "CLK/I0_1") (pintype "input"))
      (node (ref "D3") (pin "1") (pinfunction "CLK/I0_1") (pintype "input"))
      (node (ref "D4") (pin "1") (pinfunction "CLK/I0_1") (pintype "input"))
      (node (ref "D5") (pin "1") (pinfunction "CLK/I0_1") (pintype "input"))
      (node (ref "D6") (pin "1") (pinfunction "CLK/I0_1") (pintype "input"))
      (node (ref "D7") (pin "1") (pinfunction "CLK/I0_1") (pintype "input"))
      (node (ref "D8") (pin "1") (pinfunction "CLK/I0_1") (pintype "input"))
      (node (ref "D9") (pin "1") (pinfunction "CLK/I0_1") (pintype "input"))
      (node (ref "IOCTL") (pin "24") (pinfunction "24_24") (pintype "passive"))
    )
    (net (code "18") (name "CLR*") (class "Default")
      (node (ref "B11") (pin "13") (pinfunction "I10_13") (pintype "input"))
      (node (ref "FPCTL") (pin "6") (pinfunction "6_6") (pintype "passive"))
      (node (ref "R30") (pin "1") (pinfunction "1_1") (pintype "passive"))
    )
    (net (code "19") (name "CM") (class "Default")
      (node (ref "B9") (pin "9") (pinfunction "I7_9") (pintype "input"))
      (node (ref "E5") (pin "6") (pinfunction "O_6") (pintype "output"))
    )
    (net (code "20") (name "CONT*") (class "Default")
      (node (ref "B11") (pin "5") (pinfunction "I3_5") (pintype "input"))
      (node (ref "FPCTL") (pin "8") (pinfunction "8_8") (pintype "passive"))
      (node (ref "R31") (pin "1") (pinfunction "1_1") (pintype "passive"))
    )
    (net (code "21") (name "COUT_L") (class "Default")
      (node (ref "C4") (pin "16") (pinfunction "CN+4_16") (pintype "output"))
      (node (ref "E6") (pin "5") (pinfunction "I1_5") (pintype "input"))
    )
    (net (code "22") (name "DEP*") (class "Default")
      (node (ref "B11") (pin "14") (pinfunction "O0_14") (pintype "bidirectional"))
      (node (ref "FPCTL") (pin "4") (pinfunction "4_4") (pintype "passive"))
      (node (ref "R29") (pin "1") (pinfunction "1_1") (pintype "passive"))
    )
    (net (code "23") (name "EX*") (class "Default")
      (node (ref "B11") (pin "11") (pinfunction "I9_11") (pintype "input"))
      (node (ref "FPCTL") (pin "2") (pinfunction "2_2") (pintype "passive"))
      (node (ref "R28") (pin "1") (pinfunction "1_1") (pintype "passive"))
    )
    (net (code "24") (name "EXTINT") (class "Default")
      (node (ref "A0") (pin "11") (pinfunction "~{Q3}_11") (pintype "output"))
      (node (ref "E3") (pin "9") (pinfunction "I0_9") (pintype "input"))
    )
    (net (code "25") (name "F0") (class "Default")
      (node (ref "C4") (pin "13") (pinfunction "F3_13") (pintype "output"))
      (node (ref "D0") (pin "10") (pinfunction "I8_10") (pintype "input"))
    )
    (net (code "26") (name "F1") (class "Default")
      (node (ref "C4") (pin "11") (pinfunction "F2_11") (pintype "output"))
      (node (ref "D1") (pin "10") (pinfunction "I8_10") (pintype "input"))
    )
    (net (code "27") (name "F2") (class "Default")
      (node (ref "C4") (pin "10") (pinfunction "F1_10") (pintype "output"))
      (node (ref "D2") (pin "10") (pinfunction "I8_10") (pintype "input"))
    )
    (net (code "28") (name "F3") (class "Default")
      (node (ref "C4") (pin "9") (pinfunction "F0_9") (pintype "output"))
      (node (ref "D3") (pin "10") (pinfunction "I8_10") (pintype "input"))
    )
    (net (code "29") (name "F4") (class "Default")
      (node (ref "C6") (pin "13") (pinfunction "F3_13") (pintype "output"))
      (node (ref "D4") (pin "10") (pinfunction "I8_10") (pintype "input"))
    )
    (net (code "30") (name "F5") (class "Default")
      (node (ref "C6") (pin "11") (pinfunction "F2_11") (pintype "output"))
      (node (ref "D5") (pin "10") (pinfunction "I8_10") (pintype "input"))
    )
    (net (code "31") (name "F6") (class "Default")
      (node (ref "C6") (pin "10") (pinfunction "F1_10") (pintype "output"))
      (node (ref "D6") (pin "10") (pinfunction "I8_10") (pintype "input"))
    )
    (net (code "32") (name "F7") (class "Default")
      (node (ref "C6") (pin "9") (pinfunction "F0_9") (pintype "output"))
      (node (ref "D7") (pin "10") (pinfunction "I8_10") (pintype "input"))
    )
    (net (code "33") (name "F8") (class "Default")
      (node (ref "C9") (pin "13") (pinfunction "F3_13") (pintype "output"))
      (node (ref "D8") (pin "10") (pinfunction "I8_10") (pintype "input"))
    )
    (net (code "34") (name "F9") (class "Default")
      (node (ref "C9") (pin "11") (pinfunction "F2_11") (pintype "output"))
      (node (ref "D9") (pin "10") (pinfunction "I8_10") (pintype "input"))
    )
    (net (code "35") (name "F10") (class "Default")
      (node (ref "C9") (pin "10") (pinfunction "F1_10") (pintype "output"))
      (node (ref "D10") (pin "10") (pinfunction "I8_10") (pintype "input"))
    )
    (net (code "36") (name "F11") (class "Default")
      (node (ref "C9") (pin "9") (pinfunction "F0_9") (pintype "output"))
      (node (ref "D11") (pin "10") (pinfunction "I8_10") (pintype "input"))
    )
    (net (code "37") (name "GND") (class "Default")
      (node (ref "A1") (pin "2") (pinfunction "SR_2") (pintype "input"))
      (node (ref "A1") (pin "4") (pinfunction "B_4") (pintype "input"))
      (node (ref "A1") (pin "5") (pinfunction "C_5") (pintype "input"))
      (node (ref "A1") (pin "6") (pinfunction "D_6") (pintype "input"))
      (node (ref "A1") (pin "7") (pinfunction "SL_7") (pintype "input"))
      (node (ref "A2") (pin "12") (pinfunction "D7_12") (pintype "input"))
      (node (ref "A2") (pin "13") (pinfunction "D6_13") (pintype "input"))
      (node (ref "A2") (pin "7") (pinfunction "G_7") (pintype "input"))
      (node (ref "B10") (pin "13") (pinfunction "I10_13") (pintype "input"))
      (node (ref "B8") (pin "10") (pinfunction "I8_10") (pintype "input"))
      (node (ref "B8") (pin "11") (pinfunction "I9_11") (pintype "input"))
      (node (ref "B8") (pin "13") (pinfunction "I10_13") (pintype "input"))
      (node (ref "B8") (pin "8") (pinfunction "I6_8") (pintype "input"))
      (node (ref "B8") (pin "9") (pinfunction "I7_9") (pintype "input"))
      (node (ref "C1") (pin "9") (pinfunction "~{CS}_9") (pintype "input"))
      (node (ref "C10") (pin "2") (pinfunction "2_2") (pintype "passive"))
      (node (ref "C11") (pin "2") (pinfunction "2_2") (pintype "passive"))
      (node (ref "C12") (pin "2") (pinfunction "2_2") (pintype "passive"))
      (node (ref "C13") (pin "2") (pinfunction "2_2") (pintype "passive"))
      (node (ref "C14") (pin "2") (pinfunction "2_2") (pintype "passive"))
      (node (ref "C15") (pin "2") (pinfunction "2_2") (pintype "passive"))
      (node (ref "C16") (pin "2") (pinfunction "2_2") (pintype "passive"))
      (node (ref "C17") (pin "2") (pinfunction "2_2") (pintype "passive"))
      (node (ref "C18") (pin "2") (pinfunction "2_2") (pintype "passive"))
      (node (ref "C19") (pin "2") (pinfunction "2_2") (pintype "passive"))
      (node (ref "C2") (pin "9") (pinfunction "~{CS}_9") (pintype "input"))
      (node (ref "C20") (pin "2") (pinfunction "2_2") (pintype "passive"))
      (node (ref "C21") (pin "2") (pinfunction "2_2") (pintype "passive"))
      (node (ref "C22") (pin "2") (pinfunction "2_2") (pintype "passive"))
      (node (ref "C23") (pin "2") (pinfunction "2_2") (pintype "passive"))
      (node (ref "C24") (pin "2") (pinfunction "2_2") (pintype "passive"))
      (node (ref "C25") (pin "2") (pinfunction "2_2") (pintype "passive"))
      (node (ref "C26") (pin "2") (pinfunction "2_2") (pintype "passive"))
      (node (ref "C27") (pin "2") (pinfunction "2_2") (pintype "passive"))
      (node (ref "C28") (pin "2") (pinfunction "2_2") (pintype "passive"))
      (node (ref "C29") (pin "2") (pinfunction "2_2") (pintype "passive"))
      (node (ref "C3") (pin "9") (pinfunction "~{CS}_9") (pintype "input"))
      (node (ref "C30") (pin "2") (pinfunction "2_2") (pintype "passive"))
      (node (ref "C31") (pin "2") (pinfunction "2_2") (pintype "passive"))
      (node (ref "C32") (pin "2") (pinfunction "2_2") (pintype "passive"))
      (node (ref "C33") (pin "2") (pinfunction "2_2") (pintype "passive"))
      (node (ref "C34") (pin "2") (pinfunction "2_2") (pintype "passive"))
      (node (ref "C35") (pin "2") (pinfunction "2_2") (pintype "passive"))
      (node (ref "C36") (pin "2") (pinfunction "2_2") (pintype "passive"))
      (node (ref "C37") (pin "2") (pinfunction "2_2") (pintype "passive"))
      (node (ref "C38") (pin "2") (pinfunction "2_2") (pintype "passive"))
      (node (ref "C39") (pin "2") (pinfunction "2_2") (pintype "passive"))
      (node (ref "C4") (pin "4") (pinfunction "S2_4") (pintype "input"))
      (node (ref "C40") (pin "2") (pinfunction "2_2") (pintype "passive"))
      (node (ref "C41") (pin "2") (pinfunction "2_2") (pintype "passive"))
      (node (ref "C42") (pin "2") (pinfunction "2_2") (pintype "passive"))
      (node (ref "C43") (pin "2") (pinfunction "2_2") (pintype "passive"))
      (node (ref "C44") (pin "2") (pinfunction "2_2") (pintype "passive"))
      (node (ref "C45") (pin "2") (pinfunction "2_2") (pintype "passive"))
      (node (ref "C46") (pin "2") (pinfunction "2_2") (pintype "passive"))
      (node (ref "C47") (pin "2") (pinfunction "2_2") (pintype "passive"))
      (node (ref "C48") (pin "2") (pinfunction "2_2") (pintype "passive"))
      (node (ref "C49") (pin "2") (pinfunction "2_2") (pintype "passive"))
      (node (ref "C50") (pin "2") (pinfunction "2_2") (pintype "passive"))
      (node (ref "C51") (pin "2") (pinfunction "2_2") (pintype "passive"))
      (node (ref "C52") (pin "2") (pinfunction "2_2") (pintype "passive"))
      (node (ref "C6") (pin "4") (pinfunction "S2_4") (pintype "input"))
      (node (ref "C9") (pin "4") (pinfunction "S2_4") (pintype "input"))
      (node (ref "E7") (pin "11") (pinfunction "G_11") (pintype "input"))
      (node (ref "E7") (pin "12") (pinfunction "H_12") (pintype "input"))
      (node (ref "FPCTL") (pin "1") (pinfunction "1_1") (pintype "passive"))
      (node (ref "FPCTL") (pin "11") (pinfunction "11_11") (pintype "passive"))
      (node (ref "FPCTL") (pin "13") (pinfunction "13_13") (pintype "passive"))
      (node (ref "FPCTL") (pin "15") (pinfunction "15_15") (pintype "passive"))
      (node (ref "FPCTL") (pin "17") (pinfunction "17_17") (pintype "passive"))
      (node (ref "FPCTL") (pin "19") (pinfunction "19_19") (pintype "passive"))
      (node (ref "FPCTL") (pin "21") (pinfunction "21_21") (pintype "passive"))
      (node (ref "FPCTL") (pin "23") (pinfunction "23_23") (pintype "passive"))
      (node (ref "FPCTL") (pin "25") (pinfunction "25_25") (pintype "passive"))
      (node (ref "FPCTL") (pin "3") (pinfunction "3_3") (pintype "passive"))
      (node (ref "FPCTL") (pin "5") (pinfunction "5_5") (pintype "passive"))
      (node (ref "FPCTL") (pin "7") (pinfunction "7_7") (pintype "passive"))
      (node (ref "FPCTL") (pin "9") (pinfunction "9_9") (pintype "passive"))
      (node (ref "IN") (pin "1") (pinfunction "1_1") (pintype "passive"))
      (node (ref "IN") (pin "11") (pinfunction "11_11") (pintype "passive"))
      (node (ref "IN") (pin "13") (pinfunction "13_13") (pintype "passive"))
      (node (ref "IN") (pin "15") (pinfunction "15_15") (pintype "passive"))
      (node (ref "IN") (pin "17") (pinfunction "17_17") (pintype "passive"))
      (node (ref "IN") (pin "19") (pinfunction "19_19") (pintype "passive"))
      (node (ref "IN") (pin "21") (pinfunction "21_21") (pintype "passive"))
      (node (ref "IN") (pin "23") (pinfunction "23_23") (pintype "passive"))
      (node (ref "IN") (pin "25") (pinfunction "25_25") (pintype "passive"))
      (node (ref "IN") (pin "26") (pinfunction "26_26") (pintype "passive"))
      (node (ref "IN") (pin "3") (pinfunction "3_3") (pintype "passive"))
      (node (ref "IN") (pin "5") (pinfunction "5_5") (pintype "passive"))
      (node (ref "IN") (pin "7") (pinfunction "7_7") (pintype "passive"))
      (node (ref "IN") (pin "9") (pinfunction "9_9") (pintype "passive"))
      (node (ref "IOCTL") (pin "1") (pinfunction "1_1") (pintype "passive"))
      (node (ref "IOCTL") (pin "11") (pinfunction "11_11") (pintype "passive"))
      (node (ref "IOCTL") (pin "13") (pinfunction "13_13") (pintype "passive"))
      (node (ref "IOCTL") (pin "15") (pinfunction "15_15") (pintype "passive"))
      (node (ref "IOCTL") (pin "17") (pinfunction "17_17") (pintype "passive"))
      (node (ref "IOCTL") (pin "19") (pinfunction "19_19") (pintype "passive"))
      (node (ref "IOCTL") (pin "21") (pinfunction "21_21") (pintype "passive"))
      (node (ref "IOCTL") (pin "23") (pinfunction "23_23") (pintype "passive"))
      (node (ref "IOCTL") (pin "25") (pinfunction "25_25") (pintype "passive"))
      (node (ref "IOCTL") (pin "26") (pinfunction "26_26") (pintype "passive"))
      (node (ref "IOCTL") (pin "3") (pinfunction "3_3") (pintype "passive"))
      (node (ref "IOCTL") (pin "5") (pinfunction "5_5") (pintype "passive"))
      (node (ref "IOCTL") (pin "7") (pinfunction "7_7") (pintype "passive"))
      (node (ref "IOCTL") (pin "9") (pinfunction "9_9") (pintype "passive"))
      (node (ref "IR") (pin "1") (pinfunction "1_1") (pintype "passive"))
      (node (ref "IR") (pin "11") (pinfunction "11_11") (pintype "passive"))
      (node (ref "IR") (pin "13") (pinfunction "13_13") (pintype "passive"))
      (node (ref "IR") (pin "15") (pinfunction "15_15") (pintype "passive"))
      (node (ref "IR") (pin "17") (pinfunction "17_17") (pintype "passive"))
      (node (ref "IR") (pin "19") (pinfunction "19_19") (pintype "passive"))
      (node (ref "IR") (pin "21") (pinfunction "21_21") (pintype "passive"))
      (node (ref "IR") (pin "23") (pinfunction "23_23") (pintype "passive"))
      (node (ref "IR") (pin "25") (pinfunction "25_25") (pintype "passive"))
      (node (ref "IR") (pin "26") (pinfunction "26_26") (pintype "passive"))
      (node (ref "IR") (pin "3") (pinfunction "3_3") (pintype "passive"))
      (node (ref "IR") (pin "5") (pinfunction "5_5") (pintype "passive"))
      (node (ref "IR") (pin "7") (pinfunction "7_7") (pintype "passive"))
      (node (ref "IR") (pin "9") (pinfunction "9_9") (pintype "passive"))
      (node (ref "J2") (pin "1") (pinfunction "1_1") (pintype "passive"))
      (node (ref "LAC") (pin "1") (pinfunction "1_1") (pintype "passive"))
      (node (ref "LAC") (pin "11") (pinfunction "11_11") (pintype "passive"))
      (node (ref "LAC") (pin "13") (pinfunction "13_13") (pintype "passive"))
      (node (ref "LAC") (pin "15") (pinfunction "15_15") (pintype "passive"))
      (node (ref "LAC") (pin "17") (pinfunction "17_17") (pintype "passive"))
      (node (ref "LAC") (pin "19") (pinfunction "19_19") (pintype "passive"))
      (node (ref "LAC") (pin "21") (pinfunction "21_21") (pintype "passive"))
      (node (ref "LAC") (pin "23") (pinfunction "23_23") (pintype "passive"))
      (node (ref "LAC") (pin "25") (pinfunction "25_25") (pintype "passive"))
      (node (ref "LAC") (pin "3") (pinfunction "3_3") (pintype "passive"))
      (node (ref "LAC") (pin "5") (pinfunction "5_5") (pintype "passive"))
      (node (ref "LAC") (pin "7") (pinfunction "7_7") (pintype "passive"))
      (node (ref "LAC") (pin "9") (pinfunction "9_9") (pintype "passive"))
      (node (ref "LCH") (pin "1") (pinfunction "1_1") (pintype "passive"))
      (node (ref "LCH") (pin "11") (pinfunction "11_11") (pintype "passive"))
      (node (ref "LCH") (pin "13") (pinfunction "13_13") (pintype "passive"))
      (node (ref "LCH") (pin "14") (pinfunction "14_14") (pintype "passive"))
      (node (ref "LCH") (pin "15") (pinfunction "15_15") (pintype "passive"))
      (node (ref "LCH") (pin "16") (pinfunction "16_16") (pintype "passive"))
      (node (ref "LCH") (pin "17") (pinfunction "17_17") (pintype "passive"))
      (node (ref "LCH") (pin "18") (pinfunction "18_18") (pintype "passive"))
      (node (ref "LCH") (pin "19") (pinfunction "19_19") (pintype "passive"))
      (node (ref "LCH") (pin "20") (pinfunction "20_20") (pintype "passive"))
      (node (ref "LCH") (pin "21") (pinfunction "21_21") (pintype "passive"))
      (node (ref "LCH") (pin "22") (pinfunction "22_22") (pintype "passive"))
      (node (ref "LCH") (pin "23") (pinfunction "23_23") (pintype "passive"))
      (node (ref "LCH") (pin "24") (pinfunction "24_24") (pintype "passive"))
      (node (ref "LCH") (pin "25") (pinfunction "25_25") (pintype "passive"))
      (node (ref "LCH") (pin "26") (pinfunction "26_26") (pintype "passive"))
      (node (ref "LCH") (pin "3") (pinfunction "3_3") (pintype "passive"))
      (node (ref "LCH") (pin "5") (pinfunction "5_5") (pintype "passive"))
      (node (ref "LCH") (pin "7") (pinfunction "7_7") (pintype "passive"))
      (node (ref "LCH") (pin "9") (pinfunction "9_9") (pintype "passive"))
      (node (ref "MA") (pin "1") (pinfunction "1_1") (pintype "passive"))
      (node (ref "MA") (pin "11") (pinfunction "11_11") (pintype "passive"))
      (node (ref "MA") (pin "13") (pinfunction "13_13") (pintype "passive"))
      (node (ref "MA") (pin "15") (pinfunction "15_15") (pintype "passive"))
      (node (ref "MA") (pin "17") (pinfunction "17_17") (pintype "passive"))
      (node (ref "MA") (pin "19") (pinfunction "19_19") (pintype "passive"))
      (node (ref "MA") (pin "21") (pinfunction "21_21") (pintype "passive"))
      (node (ref "MA") (pin "23") (pinfunction "23_23") (pintype "passive"))
      (node (ref "MA") (pin "25") (pinfunction "25_25") (pintype "passive"))
      (node (ref "MA") (pin "26") (pinfunction "26_26") (pintype "passive"))
      (node (ref "MA") (pin "3") (pinfunction "3_3") (pintype "passive"))
      (node (ref "MA") (pin "5") (pinfunction "5_5") (pintype "passive"))
      (node (ref "MA") (pin "7") (pinfunction "7_7") (pintype "passive"))
      (node (ref "MA") (pin "9") (pinfunction "9_9") (pintype "passive"))
      (node (ref "MB") (pin "1") (pinfunction "1_1") (pintype "passive"))
      (node (ref "MB") (pin "11") (pinfunction "11_11") (pintype "passive"))
      (node (ref "MB") (pin "13") (pinfunction "13_13") (pintype "passive"))
      (node (ref "MB") (pin "15") (pinfunction "15_15") (pintype "passive"))
      (node (ref "MB") (pin "17") (pinfunction "17_17") (pintype "passive"))
      (node (ref "MB") (pin "19") (pinfunction "19_19") (pintype "passive"))
      (node (ref "MB") (pin "21") (pinfunction "21_21") (pintype "passive"))
      (node (ref "MB") (pin "23") (pinfunction "23_23") (pintype "passive"))
      (node (ref "MB") (pin "25") (pinfunction "25_25") (pintype "passive"))
      (node (ref "MB") (pin "26") (pinfunction "26_26") (pintype "passive"))
      (node (ref "MB") (pin "3") (pinfunction "3_3") (pintype "passive"))
      (node (ref "MB") (pin "5") (pinfunction "5_5") (pintype "passive"))
      (node (ref "MB") (pin "7") (pinfunction "7_7") (pintype "passive"))
      (node (ref "MB") (pin "9") (pinfunction "9_9") (pintype "passive"))
      (node (ref "MEM") (pin "1") (pinfunction "1_1") (pintype "passive"))
      (node (ref "MEM") (pin "11") (pinfunction "11_11") (pintype "passive"))
      (node (ref "MEM") (pin "13") (pinfunction "13_13") (pintype "passive"))
      (node (ref "MEM") (pin "15") (pinfunction "15_15") (pintype "passive"))
      (node (ref "MEM") (pin "17") (pinfunction "17_17") (pintype "passive"))
      (node (ref "MEM") (pin "19") (pinfunction "19_19") (pintype "passive"))
      (node (ref "MEM") (pin "21") (pinfunction "21_21") (pintype "passive"))
      (node (ref "MEM") (pin "23") (pinfunction "23_23") (pintype "passive"))
      (node (ref "MEM") (pin "25") (pinfunction "25_25") (pintype "passive"))
      (node (ref "MEM") (pin "26") (pinfunction "26_26") (pintype "passive"))
      (node (ref "MEM") (pin "3") (pinfunction "3_3") (pintype "passive"))
      (node (ref "MEM") (pin "5") (pinfunction "5_5") (pintype "passive"))
      (node (ref "MEM") (pin "7") (pinfunction "7_7") (pintype "passive"))
      (node (ref "MEM") (pin "9") (pinfunction "9_9") (pintype "passive"))
      (node (ref "PC") (pin "1") (pinfunction "1_1") (pintype "passive"))
      (node (ref "PC") (pin "11") (pinfunction "11_11") (pintype "passive"))
      (node (ref "PC") (pin "13") (pinfunction "13_13") (pintype "passive"))
      (node (ref "PC") (pin "15") (pinfunction "15_15") (pintype "passive"))
      (node (ref "PC") (pin "17") (pinfunction "17_17") (pintype "passive"))
      (node (ref "PC") (pin "19") (pinfunction "19_19") (pintype "passive"))
      (node (ref "PC") (pin "21") (pinfunction "21_21") (pintype "passive"))
      (node (ref "PC") (pin "23") (pinfunction "23_23") (pintype "passive"))
      (node (ref "PC") (pin "25") (pinfunction "25_25") (pintype "passive"))
      (node (ref "PC") (pin "26") (pinfunction "26_26") (pintype "passive"))
      (node (ref "PC") (pin "3") (pinfunction "3_3") (pintype "passive"))
      (node (ref "PC") (pin "5") (pinfunction "5_5") (pintype "passive"))
      (node (ref "PC") (pin "7") (pinfunction "7_7") (pintype "passive"))
      (node (ref "PC") (pin "9") (pinfunction "9_9") (pintype "passive"))
      (node (ref "RXS") (pin "1") (pinfunction "1_1") (pintype "passive"))
      (node (ref "RXS") (pin "11") (pinfunction "11_11") (pintype "passive"))
      (node (ref "RXS") (pin "13") (pinfunction "13_13") (pintype "passive"))
      (node (ref "RXS") (pin "15") (pinfunction "15_15") (pintype "passive"))
      (node (ref "RXS") (pin "17") (pinfunction "17_17") (pintype "passive"))
      (node (ref "RXS") (pin "19") (pinfunction "19_19") (pintype "passive"))
      (node (ref "RXS") (pin "20") (pinfunction "20_20") (pintype "passive"))
      (node (ref "RXS") (pin "21") (pinfunction "21_21") (pintype "passive"))
      (node (ref "RXS") (pin "23") (pinfunction "23_23") (pintype "passive"))
      (node (ref "RXS") (pin "24") (pinfunction "24_24") (pintype "passive"))
      (node (ref "RXS") (pin "25") (pinfunction "25_25") (pintype "passive"))
      (node (ref "RXS") (pin "26") (pinfunction "26_26") (pintype "passive"))
      (node (ref "RXS") (pin "3") (pinfunction "3_3") (pintype "passive"))
      (node (ref "RXS") (pin "5") (pinfunction "5_5") (pintype "passive"))
      (node (ref "RXS") (pin "7") (pinfunction "7_7") (pintype "passive"))
      (node (ref "RXS") (pin "9") (pinfunction "9_9") (pintype "passive"))
      (node (ref "ST") (pin "1") (pinfunction "1_1") (pintype "passive"))
      (node (ref "ST") (pin "11") (pinfunction "11_11") (pintype "passive"))
      (node (ref "ST") (pin "13") (pinfunction "13_13") (pintype "passive"))
      (node (ref "ST") (pin "15") (pinfunction "15_15") (pintype "passive"))
      (node (ref "ST") (pin "17") (pinfunction "17_17") (pintype "passive"))
      (node (ref "ST") (pin "19") (pinfunction "19_19") (pintype "passive"))
      (node (ref "ST") (pin "21") (pinfunction "21_21") (pintype "passive"))
      (node (ref "ST") (pin "23") (pinfunction "23_23") (pintype "passive"))
      (node (ref "ST") (pin "25") (pinfunction "25_25") (pintype "passive"))
      (node (ref "ST") (pin "26") (pinfunction "26_26") (pintype "passive"))
      (node (ref "ST") (pin "3") (pinfunction "3_3") (pintype "passive"))
      (node (ref "ST") (pin "5") (pinfunction "5_5") (pintype "passive"))
      (node (ref "ST") (pin "7") (pinfunction "7_7") (pintype "passive"))
      (node (ref "ST") (pin "9") (pinfunction "9_9") (pintype "passive"))
      (node (ref "SW") (pin "1") (pinfunction "1_1") (pintype "passive"))
      (node (ref "SW") (pin "11") (pinfunction "11_11") (pintype "passive"))
      (node (ref "SW") (pin "13") (pinfunction "13_13") (pintype "passive"))
      (node (ref "SW") (pin "15") (pinfunction "15_15") (pintype "passive"))
      (node (ref "SW") (pin "17") (pinfunction "17_17") (pintype "passive"))
      (node (ref "SW") (pin "19") (pinfunction "19_19") (pintype "passive"))
      (node (ref "SW") (pin "21") (pinfunction "21_21") (pintype "passive"))
      (node (ref "SW") (pin "23") (pinfunction "23_23") (pintype "passive"))
      (node (ref "SW") (pin "25") (pinfunction "25_25") (pintype "passive"))
      (node (ref "SW") (pin "3") (pinfunction "3_3") (pintype "passive"))
      (node (ref "SW") (pin "5") (pinfunction "5_5") (pintype "passive"))
      (node (ref "SW") (pin "7") (pinfunction "7_7") (pintype "passive"))
      (node (ref "SW") (pin "9") (pinfunction "9_9") (pintype "passive"))
    )
    (net (code "38") (name "HALT") (class "Default")
      (node (ref "A3") (pin "6") (pinfunction "Q_6") (pintype "output"))
      (node (ref "B11") (pin "2") (pinfunction "I0_2") (pintype "input"))
      (node (ref "B6") (pin "8") (pinfunction "I6_8") (pintype "input"))
      (node (ref "LCH") (pin "12") (pinfunction "12_12") (pintype "passive"))
    )
    (net (code "39") (name "HALT*") (class "Default")
      (node (ref "B4") (pin "8") (pinfunction "I6_8") (pintype "input"))
      (node (ref "SW") (pin "26") (pinfunction "26_26") (pintype "passive"))
    )
    (net (code "40") (name "IE") (class "Default")
      (node (ref "E3") (pin "10") (pinfunction "I1_10") (pintype "input"))
      (node (ref "E3") (pin "11") (pinfunction "O_11") (pintype "output"))
    )
    (net (code "41") (name "IE1") (class "Default")
      (node (ref "A3") (pin "10") (pinfunction "Q_10") (pintype "output"))
      (node (ref "B7") (pin "13") (pinfunction "D5_13") (pintype "input"))
      (node (ref "E3") (pin "12") (pinfunction "I0_12") (pintype "input"))
    )
    (net (code "42") (name "IE2") (class "Default")
      (node (ref "B7") (pin "12") (pinfunction "Q5_12") (pintype "output"))
      (node (ref "E3") (pin "13") (pinfunction "I1_13") (pintype "input"))
    )
    (net (code "43") (name "IERST_L") (class "Default")
      (node (ref "A3") (pin "13") (pinfunction "K_13") (pintype "input"))
      (node (ref "B4") (pin "17") (pinfunction "O3_17") (pintype "bidirectional"))
    )
    (net (code "44") (name "IESET") (class "Default")
      (node (ref "A3") (pin "14") (pinfunction "J_14") (pintype "input"))
      (node (ref "B4") (pin "18") (pinfunction "O4_18") (pintype "bidirectional"))
    )
    (net (code "45") (name "IN0") (class "Default")
      (node (ref "D0") (pin "14") (pinfunction "O0_14") (pintype "bidirectional"))
      (node (ref "IN") (pin "2") (pinfunction "2_2") (pintype "passive"))
      (node (ref "R4") (pin "1") (pinfunction "1_1") (pintype "passive"))
    )
    (net (code "46") (name "IN1") (class "Default")
      (node (ref "D1") (pin "14") (pinfunction "O0_14") (pintype "bidirectional"))
      (node (ref "IN") (pin "4") (pinfunction "4_4") (pintype "passive"))
      (node (ref "R5") (pin "1") (pinfunction "1_1") (pintype "passive"))
    )
    (net (code "47") (name "IN2") (class "Default")
      (node (ref "D2") (pin "14") (pinfunction "O0_14") (pintype "bidirectional"))
      (node (ref "IN") (pin "6") (pinfunction "6_6") (pintype "passive"))
      (node (ref "R6") (pin "1") (pinfunction "1_1") (pintype "passive"))
    )
    (net (code "48") (name "IN3") (class "Default")
      (node (ref "D3") (pin "14") (pinfunction "O0_14") (pintype "bidirectional"))
      (node (ref "IN") (pin "8") (pinfunction "8_8") (pintype "passive"))
      (node (ref "R7") (pin "1") (pinfunction "1_1") (pintype "passive"))
    )
    (net (code "49") (name "IN4") (class "Default")
      (node (ref "D4") (pin "14") (pinfunction "O0_14") (pintype "bidirectional"))
      (node (ref "IN") (pin "10") (pinfunction "10_10") (pintype "passive"))
      (node (ref "R8") (pin "1") (pinfunction "1_1") (pintype "passive"))
    )
    (net (code "50") (name "IN5") (class "Default")
      (node (ref "D5") (pin "14") (pinfunction "O0_14") (pintype "bidirectional"))
      (node (ref "IN") (pin "12") (pinfunction "12_12") (pintype "passive"))
      (node (ref "R9") (pin "1") (pinfunction "1_1") (pintype "passive"))
    )
    (net (code "51") (name "IN6") (class "Default")
      (node (ref "D6") (pin "14") (pinfunction "O0_14") (pintype "bidirectional"))
      (node (ref "IN") (pin "14") (pinfunction "14_14") (pintype "passive"))
      (node (ref "R10") (pin "1") (pinfunction "1_1") (pintype "passive"))
    )
    (net (code "52") (name "IN7") (class "Default")
      (node (ref "D7") (pin "14") (pinfunction "O0_14") (pintype "bidirectional"))
      (node (ref "IN") (pin "16") (pinfunction "16_16") (pintype "passive"))
      (node (ref "R11") (pin "1") (pinfunction "1_1") (pintype "passive"))
    )
    (net (code "53") (name "IN8") (class "Default")
      (node (ref "D8") (pin "14") (pinfunction "O0_14") (pintype "bidirectional"))
      (node (ref "IN") (pin "18") (pinfunction "18_18") (pintype "passive"))
      (node (ref "R12") (pin "1") (pinfunction "1_1") (pintype "passive"))
    )
    (net (code "54") (name "IN9") (class "Default")
      (node (ref "D9") (pin "14") (pinfunction "O0_14") (pintype "bidirectional"))
      (node (ref "IN") (pin "20") (pinfunction "20_20") (pintype "passive"))
      (node (ref "R13") (pin "1") (pinfunction "1_1") (pintype "passive"))
    )
    (net (code "55") (name "IN10") (class "Default")
      (node (ref "D10") (pin "14") (pinfunction "O0_14") (pintype "bidirectional"))
      (node (ref "IN") (pin "22") (pinfunction "22_22") (pintype "passive"))
      (node (ref "R14") (pin "1") (pinfunction "1_1") (pintype "passive"))
    )
    (net (code "56") (name "IN11") (class "Default")
      (node (ref "D11") (pin "14") (pinfunction "O0_14") (pintype "bidirectional"))
      (node (ref "IN") (pin "24") (pinfunction "24_24") (pintype "passive"))
      (node (ref "R15") (pin "1") (pinfunction "1_1") (pintype "passive"))
    )
    (net (code "57") (name "INNA") (class "Default")
      (node (ref "B10") (pin "17") (pinfunction "O3_17") (pintype "bidirectional"))
      (node (ref "B6") (pin "10") (pinfunction "I8_10") (pintype "input"))
    )
    (net (code "58") (name "INT") (class "Default")
      (node (ref "B11") (pin "3") (pinfunction "I1_3") (pintype "input"))
      (node (ref "B6") (pin "9") (pinfunction "I7_9") (pintype "input"))
      (node (ref "E3") (pin "8") (pinfunction "O_8") (pintype "output"))
    )
    (net (code "59") (name "IO4") (class "Default")
      (node (ref "A1") (pin "13") (pinfunction "QC_13") (pintype "output"))
      (node (ref "B10") (pin "11") (pinfunction "I9_11") (pintype "input"))
      (node (ref "E2") (pin "10") (pinfunction "I1_10") (pintype "input"))
    )
    (net (code "60") (name "IOCLA_L") (class "Default")
      (node (ref "B6") (pin "13") (pinfunction "I10_13") (pintype "input"))
      (node (ref "IOCTL") (pin "14") (pinfunction "14_14") (pintype "passive"))
      (node (ref "R46") (pin "1") (pinfunction "1_1") (pintype "passive"))
    )
    (net (code "61") (name "IOINT_L") (class "Default")
      (node (ref "A0") (pin "12") (pinfunction "D3_12") (pintype "input"))
      (node (ref "IOCTL") (pin "10") (pinfunction "10_10") (pintype "passive"))
      (node (ref "R44") (pin "1") (pinfunction "1_1") (pintype "passive"))
    )
    (net (code "62") (name "IOOR_L") (class "Default")
      (node (ref "B6") (pin "14") (pinfunction "O0_14") (pintype "bidirectional"))
      (node (ref "IOCTL") (pin "12") (pinfunction "12_12") (pintype "passive"))
      (node (ref "R45") (pin "1") (pinfunction "1_1") (pintype "passive"))
    )
    (net (code "63") (name "IOP1") (class "Default")
      (node (ref "E2") (pin "3") (pinfunction "O_3") (pintype "output"))
      (node (ref "LCH") (pin "2") (pinfunction "2_2") (pintype "passive"))
    )
    (net (code "64") (name "IOP2") (class "Default")
      (node (ref "E2") (pin "6") (pinfunction "O_6") (pintype "output"))
      (node (ref "LCH") (pin "4") (pinfunction "4_4") (pintype "passive"))
    )
    (net (code "65") (name "IOP4") (class "Default")
      (node (ref "E2") (pin "8") (pinfunction "O_8") (pintype "output"))
      (node (ref "LCH") (pin "6") (pinfunction "6_6") (pintype "passive"))
    )
    (net (code "66") (name "IOSKP_L") (class "Default")
      (node (ref "B5") (pin "9") (pinfunction "I7_9") (pintype "input"))
      (node (ref "IOCTL") (pin "8") (pinfunction "8_8") (pintype "passive"))
      (node (ref "R43") (pin "1") (pinfunction "1_1") (pintype "passive"))
    )
    (net (code "67") (name "IOZ") (class "Default")
      (node (ref "B10") (pin "9") (pinfunction "I7_9") (pintype "input"))
      (node (ref "E7") (pin "13") (pinfunction "W_13") (pintype "output"))
    )
    (net (code "68") (name "IR0") (class "Default")
      (node (ref "B10") (pin "5") (pinfunction "I3_5") (pintype "input"))
      (node (ref "D0") (pin "22") (pinfunction "O8_22") (pintype "bidirectional"))
      (node (ref "IR") (pin "2") (pinfunction "2_2") (pintype "passive"))
    )
    (net (code "69") (name "IR1") (class "Default")
      (node (ref "B10") (pin "6") (pinfunction "I4_6") (pintype "input"))
      (node (ref "D1") (pin "22") (pinfunction "O8_22") (pintype "bidirectional"))
      (node (ref "IR") (pin "4") (pinfunction "4_4") (pintype "passive"))
    )
    (net (code "70") (name "IR2") (class "Default")
      (node (ref "B10") (pin "7") (pinfunction "I5_7") (pintype "input"))
      (node (ref "D2") (pin "22") (pinfunction "O8_22") (pintype "bidirectional"))
      (node (ref "IR") (pin "6") (pinfunction "6_6") (pintype "passive"))
    )
    (net (code "71") (name "IR3") (class "Default")
      (node (ref "B10") (pin "8") (pinfunction "I6_8") (pintype "input"))
      (node (ref "D3") (pin "22") (pinfunction "O8_22") (pintype "bidirectional"))
      (node (ref "E7") (pin "2") (pinfunction "A_2") (pintype "input"))
      (node (ref "IR") (pin "8") (pinfunction "8_8") (pintype "passive"))
    )
    (net (code "72") (name "IR4") (class "Default")
      (node (ref "B5") (pin "11") (pinfunction "I9_11") (pintype "input"))
      (node (ref "B6") (pin "15") (pinfunction "O1_15") (pintype "bidirectional"))
      (node (ref "D4") (pin "22") (pinfunction "O8_22") (pintype "bidirectional"))
      (node (ref "E5") (pin "1") (pinfunction "I0_1") (pintype "input"))
      (node (ref "E7") (pin "3") (pinfunction "B_3") (pintype "input"))
      (node (ref "IR") (pin "10") (pinfunction "10_10") (pintype "passive"))
    )
    (net (code "73") (name "IR5") (class "Default")
      (node (ref "B6") (pin "16") (pinfunction "O2_16") (pintype "bidirectional"))
      (node (ref "D5") (pin "22") (pinfunction "O8_22") (pintype "bidirectional"))
      (node (ref "E0") (pin "1") (pinfunction "I0_1") (pintype "input"))
      (node (ref "E1") (pin "3") (pinfunction "I1_3") (pintype "input"))
      (node (ref "E4") (pin "3") (pinfunction "I0_3") (pintype "input"))
      (node (ref "E5") (pin "2") (pinfunction "I1_2") (pintype "input"))
      (node (ref "E7") (pin "4") (pinfunction "C_4") (pintype "input"))
      (node (ref "IR") (pin "12") (pinfunction "12_12") (pintype "passive"))
    )
    (net (code "74") (name "IR6") (class "Default")
      (node (ref "D6") (pin "22") (pinfunction "O8_22") (pintype "bidirectional"))
      (node (ref "E5") (pin "4") (pinfunction "I0_4") (pintype "input"))
      (node (ref "E7") (pin "5") (pinfunction "D_5") (pintype "input"))
      (node (ref "IR") (pin "14") (pinfunction "14_14") (pintype "passive"))
    )
    (net (code "75") (name "IR7") (class "Default")
      (node (ref "D7") (pin "22") (pinfunction "O8_22") (pintype "bidirectional"))
      (node (ref "E0") (pin "4") (pinfunction "I0_4") (pintype "input"))
      (node (ref "E5") (pin "5") (pinfunction "I1_5") (pintype "input"))
      (node (ref "E6") (pin "2") (pinfunction "I1_2") (pintype "input"))
      (node (ref "E7") (pin "9") (pinfunction "E_9") (pintype "input"))
      (node (ref "IR") (pin "16") (pinfunction "16_16") (pintype "passive"))
    )
    (net (code "76") (name "IR8") (class "Default")
      (node (ref "B4") (pin "11") (pinfunction "I9_11") (pintype "input"))
      (node (ref "B6") (pin "11") (pinfunction "I9_11") (pintype "input"))
      (node (ref "D8") (pin "22") (pinfunction "O8_22") (pintype "bidirectional"))
      (node (ref "E5") (pin "9") (pinfunction "I0_9") (pintype "input"))
      (node (ref "E6") (pin "10") (pinfunction "I1_10") (pintype "input"))
      (node (ref "E7") (pin "10") (pinfunction "F_10") (pintype "input"))
      (node (ref "IR") (pin "18") (pinfunction "18_18") (pintype "passive"))
    )
    (net (code "77") (name "IR9") (class "Default")
      (node (ref "B5") (pin "13") (pinfunction "I10_13") (pintype "input"))
      (node (ref "D9") (pin "22") (pinfunction "O8_22") (pintype "bidirectional"))
      (node (ref "E2") (pin "9") (pinfunction "I0_9") (pintype "input"))
      (node (ref "E5") (pin "10") (pinfunction "I1_10") (pintype "input"))
      (node (ref "IR") (pin "20") (pinfunction "20_20") (pintype "passive"))
    )
    (net (code "78") (name "IR10") (class "Default")
      (node (ref "B4") (pin "10") (pinfunction "I8_10") (pintype "input"))
      (node (ref "B9") (pin "13") (pinfunction "I10_13") (pintype "input"))
      (node (ref "D10") (pin "22") (pinfunction "O8_22") (pintype "bidirectional"))
      (node (ref "E2") (pin "4") (pinfunction "I0_4") (pintype "input"))
      (node (ref "IR") (pin "22") (pinfunction "22_22") (pintype "passive"))
    )
    (net (code "79") (name "IR11") (class "Default")
      (node (ref "B10") (pin "10") (pinfunction "I8_10") (pintype "input"))
      (node (ref "B9") (pin "10") (pinfunction "I8_10") (pintype "input"))
      (node (ref "D11") (pin "22") (pinfunction "O8_22") (pintype "bidirectional"))
      (node (ref "E2") (pin "1") (pinfunction "I0_1") (pintype "input"))
      (node (ref "IR") (pin "24") (pinfunction "24_24") (pintype "passive"))
    )
    (net (code "80") (name "L0") (class "Default")
      (node (ref "A2") (pin "11") (pinfunction "A_11") (pintype "input"))
      (node (ref "B4") (pin "21") (pinfunction "O7_21") (pintype "bidirectional"))
      (node (ref "IOCTL") (pin "2") (pinfunction "2_2") (pintype "passive"))
    )
    (net (code "81") (name "L1") (class "Default")
      (node (ref "A2") (pin "10") (pinfunction "B_10") (pintype "input"))
      (node (ref "B4") (pin "22") (pinfunction "O8_22") (pintype "bidirectional"))
      (node (ref "IOCTL") (pin "4") (pinfunction "4_4") (pintype "passive"))
    )
    (net (code "82") (name "L2") (class "Default")
      (node (ref "A2") (pin "9") (pinfunction "C_9") (pintype "input"))
      (node (ref "B4") (pin "23") (pinfunction "O9_23") (pintype "bidirectional"))
      (node (ref "IOCTL") (pin "6") (pinfunction "6_6") (pintype "passive"))
    )
    (net (code "83") (name "LDAC*") (class "Default")
      (node (ref "B11") (pin "9") (pinfunction "I7_9") (pintype "input"))
      (node (ref "B8") (pin "15") (pinfunction "O1_15") (pintype "bidirectional"))
      (node (ref "FPCTL") (pin "20") (pinfunction "20_20") (pintype "passive"))
      (node (ref "R37") (pin "1") (pinfunction "1_1") (pintype "passive"))
    )
    (net (code "84") (name "LDIOP") (class "Default")
      (node (ref "B10") (pin "14") (pinfunction "O0_14") (pintype "bidirectional"))
      (node (ref "B4") (pin "13") (pinfunction "I10_13") (pintype "input"))
    )
    (net (code "85") (name "LDIR*") (class "Default")
      (node (ref "B11") (pin "6") (pinfunction "I4_6") (pintype "input"))
      (node (ref "FPCTL") (pin "14") (pinfunction "14_14") (pintype "passive"))
      (node (ref "R34") (pin "1") (pinfunction "1_1") (pintype "passive"))
    )
    (net (code "86") (name "LDMA*") (class "Default")
      (node (ref "B11") (pin "8") (pinfunction "I6_8") (pintype "input"))
      (node (ref "FPCTL") (pin "18") (pinfunction "18_18") (pintype "passive"))
      (node (ref "R36") (pin "1") (pinfunction "1_1") (pintype "passive"))
    )
    (net (code "87") (name "LDMB*") (class "Default")
      (node (ref "B11") (pin "7") (pinfunction "I5_7") (pintype "input"))
      (node (ref "B8") (pin "16") (pinfunction "O2_16") (pintype "bidirectional"))
      (node (ref "FPCTL") (pin "16") (pinfunction "16_16") (pintype "passive"))
      (node (ref "R35") (pin "1") (pinfunction "1_1") (pintype "passive"))
    )
    (net (code "88") (name "LDMEM*") (class "Default")
      (node (ref "B11") (pin "15") (pinfunction "O1_15") (pintype "bidirectional"))
      (node (ref "FPCTL") (pin "26") (pinfunction "26_26") (pintype "passive"))
      (node (ref "R40") (pin "1") (pinfunction "1_1") (pintype "passive"))
    )
    (net (code "89") (name "LDPC*") (class "Default")
      (node (ref "B11") (pin "10") (pinfunction "I8_10") (pintype "input"))
      (node (ref "B8") (pin "17") (pinfunction "O3_17") (pintype "bidirectional"))
      (node (ref "FPCTL") (pin "22") (pinfunction "22_22") (pintype "passive"))
      (node (ref "R38") (pin "1") (pinfunction "1_1") (pintype "passive"))
    )
    (net (code "90") (name "LINK") (class "Default")
      (node (ref "A0") (pin "2") (pinfunction "Q1_2") (pintype "output"))
      (node (ref "A2") (pin "4") (pinfunction "D0_4") (pintype "input"))
      (node (ref "D0") (pin "11") (pinfunction "I9_11") (pintype "input"))
      (node (ref "D11") (pin "13") (pinfunction "I10_13") (pintype "input"))
      (node (ref "E0") (pin "5") (pinfunction "I1_5") (pintype "input"))
      (node (ref "E6") (pin "1") (pinfunction "I0_1") (pintype "input"))
      (node (ref "LAC") (pin "26") (pinfunction "26_26") (pintype "passive"))
    )
    (net (code "91") (name "LINK&CLL") (class "Default")
      (node (ref "A2") (pin "3") (pinfunction "D1_3") (pintype "input"))
      (node (ref "E1") (pin "1") (pinfunction "O_1") (pintype "output"))
    )
    (net (code "92") (name "LINK^C") (class "Default")
      (node (ref "A2") (pin "1") (pinfunction "D3_1") (pintype "input"))
      (node (ref "E6") (pin "6") (pinfunction "O_6") (pintype "output"))
    )
    (net (code "93") (name "LINK^CML") (class "Default")
      (node (ref "A2") (pin "2") (pinfunction "D2_2") (pintype "input"))
      (node (ref "E6") (pin "3") (pinfunction "O_3") (pintype "output"))
    )
    (net (code "94") (name "LINK_L") (class "Default")
      (node (ref "A0") (pin "3") (pinfunction "~{Q1}_3") (pintype "output"))
      (node (ref "E1") (pin "2") (pinfunction "I0_2") (pintype "input"))
      (node (ref "E6") (pin "4") (pinfunction "I0_4") (pintype "input"))
    )
    (net (code "95") (name "LIOP") (class "Default")
      (node (ref "A1") (pin "10") (pinfunction "S1_10") (pintype "input"))
      (node (ref "B4") (pin "15") (pinfunction "O1_15") (pintype "bidirectional"))
    )
    (net (code "96") (name "M") (class "Default")
      (node (ref "B5") (pin "17") (pinfunction "O3_17") (pintype "bidirectional"))
      (node (ref "C4") (pin "8") (pinfunction "M_8") (pintype "input"))
      (node (ref "C6") (pin "8") (pinfunction "M_8") (pintype "input"))
      (node (ref "C9") (pin "8") (pinfunction "M_8") (pintype "input"))
      (node (ref "LCH") (pin "10") (pinfunction "10_10") (pintype "passive"))
    )
    (net (code "97") (name "MA0") (class "Default")
      (node (ref "C1") (pin "16") (pinfunction "A0_16") (pintype "input"))
      (node (ref "C2") (pin "16") (pinfunction "A0_16") (pintype "input"))
      (node (ref "C3") (pin "16") (pinfunction "A0_16") (pintype "input"))
      (node (ref "D0") (pin "20") (pinfunction "O6_20") (pintype "bidirectional"))
      (node (ref "E8") (pin "2") (pinfunction "A_2") (pintype "input"))
      (node (ref "MA") (pin "2") (pinfunction "2_2") (pintype "passive"))
    )
    (net (code "98") (name "MA1") (class "Default")
      (node (ref "C1") (pin "17") (pinfunction "A1_17") (pintype "input"))
      (node (ref "C2") (pin "17") (pinfunction "A1_17") (pintype "input"))
      (node (ref "C3") (pin "17") (pinfunction "A1_17") (pintype "input"))
      (node (ref "D1") (pin "20") (pinfunction "O6_20") (pintype "bidirectional"))
      (node (ref "E8") (pin "3") (pinfunction "B_3") (pintype "input"))
      (node (ref "MA") (pin "4") (pinfunction "4_4") (pintype "passive"))
    )
    (net (code "99") (name "MA2") (class "Default")
      (node (ref "C1") (pin "18") (pinfunction "A2_18") (pintype "input"))
      (node (ref "C2") (pin "18") (pinfunction "A2_18") (pintype "input"))
      (node (ref "C3") (pin "18") (pinfunction "A2_18") (pintype "input"))
      (node (ref "D2") (pin "20") (pinfunction "O6_20") (pintype "bidirectional"))
      (node (ref "E8") (pin "4") (pinfunction "C_4") (pintype "input"))
      (node (ref "MA") (pin "6") (pinfunction "6_6") (pintype "passive"))
    )
    (net (code "100") (name "MA3") (class "Default")
      (node (ref "C1") (pin "19") (pinfunction "A3_19") (pintype "input"))
      (node (ref "C2") (pin "19") (pinfunction "A3_19") (pintype "input"))
      (node (ref "C3") (pin "19") (pinfunction "A3_19") (pintype "input"))
      (node (ref "D3") (pin "20") (pinfunction "O6_20") (pintype "bidirectional"))
      (node (ref "E8") (pin "5") (pinfunction "D_5") (pintype "input"))
      (node (ref "MA") (pin "8") (pinfunction "8_8") (pintype "passive"))
    )
    (net (code "101") (name "MA4") (class "Default")
      (node (ref "C1") (pin "1") (pinfunction "A4_1") (pintype "input"))
      (node (ref "C2") (pin "1") (pinfunction "A4_1") (pintype "input"))
      (node (ref "C3") (pin "1") (pinfunction "A4_1") (pintype "input"))
      (node (ref "D4") (pin "20") (pinfunction "O6_20") (pintype "bidirectional"))
      (node (ref "E8") (pin "9") (pinfunction "E_9") (pintype "input"))
      (node (ref "MA") (pin "10") (pinfunction "10_10") (pintype "passive"))
    )
    (net (code "102") (name "MA5") (class "Default")
      (node (ref "C1") (pin "2") (pinfunction "A5_2") (pintype "input"))
      (node (ref "C2") (pin "2") (pinfunction "A5_2") (pintype "input"))
      (node (ref "C3") (pin "2") (pinfunction "A5_2") (pintype "input"))
      (node (ref "D5") (pin "20") (pinfunction "O6_20") (pintype "bidirectional"))
      (node (ref "E8") (pin "10") (pinfunction "F_10") (pintype "input"))
      (node (ref "MA") (pin "12") (pinfunction "12_12") (pintype "passive"))
    )
    (net (code "103") (name "MA6") (class "Default")
      (node (ref "C1") (pin "3") (pinfunction "A6_3") (pintype "input"))
      (node (ref "C2") (pin "3") (pinfunction "A6_3") (pintype "input"))
      (node (ref "C3") (pin "3") (pinfunction "A6_3") (pintype "input"))
      (node (ref "D6") (pin "20") (pinfunction "O6_20") (pintype "bidirectional"))
      (node (ref "E8") (pin "11") (pinfunction "G_11") (pintype "input"))
      (node (ref "MA") (pin "14") (pinfunction "14_14") (pintype "passive"))
    )
    (net (code "104") (name "MA7") (class "Default")
      (node (ref "C1") (pin "4") (pinfunction "A7_4") (pintype "input"))
      (node (ref "C2") (pin "4") (pinfunction "A7_4") (pintype "input"))
      (node (ref "C3") (pin "4") (pinfunction "A7_4") (pintype "input"))
      (node (ref "D7") (pin "20") (pinfunction "O6_20") (pintype "bidirectional"))
      (node (ref "E8") (pin "12") (pinfunction "H_12") (pintype "input"))
      (node (ref "MA") (pin "16") (pinfunction "16_16") (pintype "passive"))
    )
    (net (code "105") (name "MA8") (class "Default")
      (node (ref "C1") (pin "5") (pinfunction "A8_5") (pintype "input"))
      (node (ref "C2") (pin "5") (pinfunction "A8_5") (pintype "input"))
      (node (ref "C3") (pin "5") (pinfunction "A8_5") (pintype "input"))
      (node (ref "D8") (pin "20") (pinfunction "O6_20") (pintype "bidirectional"))
      (node (ref "E3") (pin "1") (pinfunction "I0_1") (pintype "input"))
      (node (ref "MA") (pin "18") (pinfunction "18_18") (pintype "passive"))
    )
    (net (code "106") (name "MA9") (class "Default")
      (node (ref "C1") (pin "6") (pinfunction "A9_6") (pintype "input"))
      (node (ref "C2") (pin "6") (pinfunction "A9_6") (pintype "input"))
      (node (ref "C3") (pin "6") (pinfunction "A9_6") (pintype "input"))
      (node (ref "D9") (pin "20") (pinfunction "O6_20") (pintype "bidirectional"))
      (node (ref "MA") (pin "20") (pinfunction "20_20") (pintype "passive"))
    )
    (net (code "107") (name "MA10") (class "Default")
      (node (ref "C1") (pin "7") (pinfunction "A10_7") (pintype "input"))
      (node (ref "C2") (pin "7") (pinfunction "A10_7") (pintype "input"))
      (node (ref "C3") (pin "7") (pinfunction "A10_7") (pintype "input"))
      (node (ref "D10") (pin "20") (pinfunction "O6_20") (pintype "bidirectional"))
      (node (ref "MA") (pin "22") (pinfunction "22_22") (pintype "passive"))
    )
    (net (code "108") (name "MA11") (class "Default")
      (node (ref "C1") (pin "8") (pinfunction "A11_8") (pintype "input"))
      (node (ref "C2") (pin "8") (pinfunction "A11_8") (pintype "input"))
      (node (ref "C3") (pin "8") (pinfunction "A11_8") (pintype "input"))
      (node (ref "D11") (pin "20") (pinfunction "O6_20") (pintype "bidirectional"))
      (node (ref "MA") (pin "24") (pinfunction "24_24") (pintype "passive"))
    )
    (net (code "109") (name "MANOR") (class "Default")
      (node (ref "A0") (pin "7") (pinfunction "Q2_7") (pintype "output"))
      (node (ref "B7") (pin "8") (pinfunction "D4_8") (pintype "input"))
    )
    (net (code "110") (name "MANOR*") (class "Default")
      (node (ref "A0") (pin "5") (pinfunction "D2_5") (pintype "input"))
      (node (ref "B11") (pin "16") (pinfunction "O2_16") (pintype "bidirectional"))
      (node (ref "FPCTL") (pin "24") (pinfunction "24_24") (pintype "passive"))
      (node (ref "R39") (pin "1") (pinfunction "1_1") (pintype "passive"))
    )
    (net (code "111") (name "MANOR_L") (class "Default")
      (node (ref "A0") (pin "6") (pinfunction "~{Q2}_6") (pintype "output"))
      (node (ref "E1") (pin "6") (pinfunction "I1_6") (pintype "input"))
    )
    (net (code "112") (name "MANP") (class "Default")
      (node (ref "B11") (pin "4") (pinfunction "I2_4") (pintype "input"))
      (node (ref "E1") (pin "4") (pinfunction "O_4") (pintype "output"))
    )
    (net (code "113") (name "MANSTOP") (class "Default")
      (node (ref "B7") (pin "9") (pinfunction "Q4_9") (pintype "output"))
      (node (ref "E1") (pin "5") (pinfunction "I0_5") (pintype "input"))
    )
    (net (code "114") (name "MB0") (class "Default")
      (node (ref "D0") (pin "21") (pinfunction "O7_21") (pintype "bidirectional"))
      (node (ref "E9") (pin "2") (pinfunction "A_2") (pintype "input"))
      (node (ref "MB") (pin "2") (pinfunction "2_2") (pintype "passive"))
    )
    (net (code "115") (name "MB1") (class "Default")
      (node (ref "D1") (pin "21") (pinfunction "O7_21") (pintype "bidirectional"))
      (node (ref "E9") (pin "3") (pinfunction "B_3") (pintype "input"))
      (node (ref "MB") (pin "4") (pinfunction "4_4") (pintype "passive"))
    )
    (net (code "116") (name "MB2") (class "Default")
      (node (ref "D2") (pin "21") (pinfunction "O7_21") (pintype "bidirectional"))
      (node (ref "E9") (pin "4") (pinfunction "C_4") (pintype "input"))
      (node (ref "MB") (pin "6") (pinfunction "6_6") (pintype "passive"))
    )
    (net (code "117") (name "MB3") (class "Default")
      (node (ref "D3") (pin "21") (pinfunction "O7_21") (pintype "bidirectional"))
      (node (ref "E9") (pin "5") (pinfunction "D_5") (pintype "input"))
      (node (ref "MB") (pin "8") (pinfunction "8_8") (pintype "passive"))
    )
    (net (code "118") (name "MB4") (class "Default")
      (node (ref "D4") (pin "21") (pinfunction "O7_21") (pintype "bidirectional"))
      (node (ref "E9") (pin "9") (pinfunction "E_9") (pintype "input"))
      (node (ref "MB") (pin "10") (pinfunction "10_10") (pintype "passive"))
    )
    (net (code "119") (name "MB5") (class "Default")
      (node (ref "D5") (pin "21") (pinfunction "O7_21") (pintype "bidirectional"))
      (node (ref "E9") (pin "10") (pinfunction "F_10") (pintype "input"))
      (node (ref "MB") (pin "12") (pinfunction "12_12") (pintype "passive"))
    )
    (net (code "120") (name "MB6") (class "Default")
      (node (ref "D6") (pin "21") (pinfunction "O7_21") (pintype "bidirectional"))
      (node (ref "E9") (pin "11") (pinfunction "G_11") (pintype "input"))
      (node (ref "MB") (pin "14") (pinfunction "14_14") (pintype "passive"))
    )
    (net (code "121") (name "MB7") (class "Default")
      (node (ref "D7") (pin "21") (pinfunction "O7_21") (pintype "bidirectional"))
      (node (ref "E9") (pin "12") (pinfunction "H_12") (pintype "input"))
      (node (ref "MB") (pin "16") (pinfunction "16_16") (pintype "passive"))
    )
    (net (code "122") (name "MB8") (class "Default")
      (node (ref "D8") (pin "21") (pinfunction "O7_21") (pintype "bidirectional"))
      (node (ref "E11") (pin "1") (pinfunction "I0_1") (pintype "input"))
      (node (ref "MB") (pin "18") (pinfunction "18_18") (pintype "passive"))
    )
    (net (code "123") (name "MB9") (class "Default")
      (node (ref "D9") (pin "21") (pinfunction "O7_21") (pintype "bidirectional"))
      (node (ref "E11") (pin "2") (pinfunction "I1_2") (pintype "input"))
      (node (ref "MB") (pin "20") (pinfunction "20_20") (pintype "passive"))
    )
    (net (code "124") (name "MB10") (class "Default")
      (node (ref "D10") (pin "21") (pinfunction "O7_21") (pintype "bidirectional"))
      (node (ref "E11") (pin "4") (pinfunction "I2_4") (pintype "input"))
      (node (ref "MB") (pin "22") (pinfunction "22_22") (pintype "passive"))
    )
    (net (code "125") (name "MB11") (class "Default")
      (node (ref "D11") (pin "21") (pinfunction "O7_21") (pintype "bidirectional"))
      (node (ref "E11") (pin "5") (pinfunction "I3_5") (pintype "input"))
      (node (ref "MB") (pin "24") (pinfunction "24_24") (pintype "passive"))
    )
    (net (code "126") (name "MBZ") (class "Default")
      (node (ref "B5") (pin "8") (pinfunction "I6_8") (pintype "input"))
      (node (ref "E3") (pin "6") (pinfunction "O_6") (pintype "output"))
    )
    (net (code "127") (name "MEM0") (class "Default")
      (node (ref "C1") (pin "15") (pinfunction "D0_15") (pintype "bidirectional"))
      (node (ref "D0") (pin "23") (pinfunction "O9_23") (pintype "bidirectional"))
      (node (ref "MEM") (pin "2") (pinfunction "2_2") (pintype "passive"))
    )
    (net (code "128") (name "MEM1") (class "Default")
      (node (ref "C1") (pin "14") (pinfunction "D1_14") (pintype "bidirectional"))
      (node (ref "D1") (pin "23") (pinfunction "O9_23") (pintype "bidirectional"))
      (node (ref "MEM") (pin "4") (pinfunction "4_4") (pintype "passive"))
    )
    (net (code "129") (name "MEM2") (class "Default")
      (node (ref "C1") (pin "13") (pinfunction "D2_13") (pintype "bidirectional"))
      (node (ref "D2") (pin "23") (pinfunction "O9_23") (pintype "bidirectional"))
      (node (ref "MEM") (pin "6") (pinfunction "6_6") (pintype "passive"))
    )
    (net (code "130") (name "MEM3") (class "Default")
      (node (ref "C1") (pin "12") (pinfunction "D3_12") (pintype "bidirectional"))
      (node (ref "D3") (pin "23") (pinfunction "O9_23") (pintype "bidirectional"))
      (node (ref "MEM") (pin "8") (pinfunction "8_8") (pintype "passive"))
    )
    (net (code "131") (name "MEM4") (class "Default")
      (node (ref "C2") (pin "15") (pinfunction "D0_15") (pintype "bidirectional"))
      (node (ref "D0") (pin "9") (pinfunction "I7_9") (pintype "input"))
      (node (ref "D1") (pin "9") (pinfunction "I7_9") (pintype "input"))
      (node (ref "D10") (pin "9") (pinfunction "I7_9") (pintype "input"))
      (node (ref "D11") (pin "9") (pinfunction "I7_9") (pintype "input"))
      (node (ref "D2") (pin "9") (pinfunction "I7_9") (pintype "input"))
      (node (ref "D3") (pin "9") (pinfunction "I7_9") (pintype "input"))
      (node (ref "D4") (pin "23") (pinfunction "O9_23") (pintype "bidirectional"))
      (node (ref "D4") (pin "9") (pinfunction "I7_9") (pintype "input"))
      (node (ref "D5") (pin "9") (pinfunction "I7_9") (pintype "input"))
      (node (ref "D6") (pin "9") (pinfunction "I7_9") (pintype "input"))
      (node (ref "D7") (pin "9") (pinfunction "I7_9") (pintype "input"))
      (node (ref "D8") (pin "9") (pinfunction "I7_9") (pintype "input"))
      (node (ref "D9") (pin "9") (pinfunction "I7_9") (pintype "input"))
      (node (ref "MEM") (pin "10") (pinfunction "10_10") (pintype "passive"))
    )
    (net (code "132") (name "MEM5") (class "Default")
      (node (ref "C2") (pin "14") (pinfunction "D1_14") (pintype "bidirectional"))
      (node (ref "D5") (pin "23") (pinfunction "O9_23") (pintype "bidirectional"))
      (node (ref "MEM") (pin "12") (pinfunction "12_12") (pintype "passive"))
    )
    (net (code "133") (name "MEM6") (class "Default")
      (node (ref "C2") (pin "13") (pinfunction "D2_13") (pintype "bidirectional"))
      (node (ref "D6") (pin "23") (pinfunction "O9_23") (pintype "bidirectional"))
      (node (ref "MEM") (pin "14") (pinfunction "14_14") (pintype "passive"))
    )
    (net (code "134") (name "MEM7") (class "Default")
      (node (ref "C2") (pin "12") (pinfunction "D3_12") (pintype "bidirectional"))
      (node (ref "D7") (pin "23") (pinfunction "O9_23") (pintype "bidirectional"))
      (node (ref "MEM") (pin "16") (pinfunction "16_16") (pintype "passive"))
    )
    (net (code "135") (name "MEM8") (class "Default")
      (node (ref "C3") (pin "15") (pinfunction "D0_15") (pintype "bidirectional"))
      (node (ref "D8") (pin "23") (pinfunction "O9_23") (pintype "bidirectional"))
      (node (ref "MEM") (pin "18") (pinfunction "18_18") (pintype "passive"))
    )
    (net (code "136") (name "MEM9") (class "Default")
      (node (ref "C3") (pin "14") (pinfunction "D1_14") (pintype "bidirectional"))
      (node (ref "D9") (pin "23") (pinfunction "O9_23") (pintype "bidirectional"))
      (node (ref "MEM") (pin "20") (pinfunction "20_20") (pintype "passive"))
    )
    (net (code "137") (name "MEM10") (class "Default")
      (node (ref "C3") (pin "13") (pinfunction "D2_13") (pintype "bidirectional"))
      (node (ref "D10") (pin "23") (pinfunction "O9_23") (pintype "bidirectional"))
      (node (ref "MEM") (pin "22") (pinfunction "22_22") (pintype "passive"))
    )
    (net (code "138") (name "MEM11") (class "Default")
      (node (ref "C3") (pin "12") (pinfunction "D3_12") (pintype "bidirectional"))
      (node (ref "D11") (pin "23") (pinfunction "O9_23") (pintype "bidirectional"))
      (node (ref "MEM") (pin "24") (pinfunction "24_24") (pintype "passive"))
    )
    (net (code "139") (name "MUX0") (class "Default")
      (node (ref "C4") (pin "19") (pinfunction "A3_19") (pintype "input"))
      (node (ref "D0") (pin "17") (pinfunction "O3_17") (pintype "bidirectional"))
    )
    (net (code "140") (name "MUX1") (class "Default")
      (node (ref "C4") (pin "21") (pinfunction "A2_21") (pintype "input"))
      (node (ref "D1") (pin "17") (pinfunction "O3_17") (pintype "bidirectional"))
    )
    (net (code "141") (name "MUX2") (class "Default")
      (node (ref "C4") (pin "23") (pinfunction "A1_23") (pintype "input"))
      (node (ref "D2") (pin "17") (pinfunction "O3_17") (pintype "bidirectional"))
    )
    (net (code "142") (name "MUX3") (class "Default")
      (node (ref "C4") (pin "2") (pinfunction "A0_2") (pintype "input"))
      (node (ref "D3") (pin "17") (pinfunction "O3_17") (pintype "bidirectional"))
    )
    (net (code "143") (name "MUX4") (class "Default")
      (node (ref "C6") (pin "19") (pinfunction "A3_19") (pintype "input"))
      (node (ref "D4") (pin "17") (pinfunction "O3_17") (pintype "bidirectional"))
    )
    (net (code "144") (name "MUX5") (class "Default")
      (node (ref "C6") (pin "21") (pinfunction "A2_21") (pintype "input"))
      (node (ref "D5") (pin "17") (pinfunction "O3_17") (pintype "bidirectional"))
    )
    (net (code "145") (name "MUX6") (class "Default")
      (node (ref "C6") (pin "23") (pinfunction "A1_23") (pintype "input"))
      (node (ref "D6") (pin "17") (pinfunction "O3_17") (pintype "bidirectional"))
    )
    (net (code "146") (name "MUX7") (class "Default")
      (node (ref "C6") (pin "2") (pinfunction "A0_2") (pintype "input"))
      (node (ref "D7") (pin "17") (pinfunction "O3_17") (pintype "bidirectional"))
    )
    (net (code "147") (name "MUX8") (class "Default")
      (node (ref "C9") (pin "19") (pinfunction "A3_19") (pintype "input"))
      (node (ref "D8") (pin "17") (pinfunction "O3_17") (pintype "bidirectional"))
    )
    (net (code "148") (name "MUX9") (class "Default")
      (node (ref "C9") (pin "21") (pinfunction "A2_21") (pintype "input"))
      (node (ref "D9") (pin "17") (pinfunction "O3_17") (pintype "bidirectional"))
    )
    (net (code "149") (name "MUX10") (class "Default")
      (node (ref "C9") (pin "23") (pinfunction "A1_23") (pintype "input"))
      (node (ref "D10") (pin "17") (pinfunction "O3_17") (pintype "bidirectional"))
    )
    (net (code "150") (name "MUX11") (class "Default")
      (node (ref "C9") (pin "2") (pinfunction "A0_2") (pintype "input"))
      (node (ref "D11") (pin "17") (pinfunction "O3_17") (pintype "bidirectional"))
    )
    (net (code "151") (name "NEWLINK") (class "Default")
      (node (ref "A0") (pin "4") (pinfunction "D1_4") (pintype "input"))
      (node (ref "A2") (pin "5") (pinfunction "Y_5") (pintype "output"))
    )
    (net (code "152") (name "NX0") (class "Default")
      (node (ref "B10") (pin "18") (pinfunction "O4_18") (pintype "bidirectional"))
      (node (ref "B11") (pin "18") (pinfunction "O4_18") (pintype "bidirectional"))
      (node (ref "B7") (pin "14") (pinfunction "D6_14") (pintype "input"))
      (node (ref "B8") (pin "18") (pinfunction "O4_18") (pintype "bidirectional"))
      (node (ref "B9") (pin "18") (pinfunction "O4_18") (pintype "bidirectional"))
      (node (ref "ST") (pin "12") (pinfunction "12_12") (pintype "passive"))
    )
    (net (code "153") (name "NX1") (class "Default")
      (node (ref "B10") (pin "19") (pinfunction "O5_19") (pintype "bidirectional"))
      (node (ref "B11") (pin "19") (pinfunction "O5_19") (pintype "bidirectional"))
      (node (ref "B7") (pin "7") (pinfunction "D3_7") (pintype "input"))
      (node (ref "B8") (pin "19") (pinfunction "O5_19") (pintype "bidirectional"))
      (node (ref "B9") (pin "19") (pinfunction "O5_19") (pintype "bidirectional"))
      (node (ref "ST") (pin "10") (pinfunction "10_10") (pintype "passive"))
    )
    (net (code "154") (name "NX2") (class "Default")
      (node (ref "B10") (pin "20") (pinfunction "O6_20") (pintype "bidirectional"))
      (node (ref "B11") (pin "20") (pinfunction "O6_20") (pintype "bidirectional"))
      (node (ref "B7") (pin "17") (pinfunction "D7_17") (pintype "input"))
      (node (ref "B8") (pin "20") (pinfunction "O6_20") (pintype "bidirectional"))
      (node (ref "B9") (pin "20") (pinfunction "O6_20") (pintype "bidirectional"))
      (node (ref "ST") (pin "8") (pinfunction "8_8") (pintype "passive"))
    )
    (net (code "155") (name "NX3") (class "Default")
      (node (ref "B10") (pin "21") (pinfunction "O7_21") (pintype "bidirectional"))
      (node (ref "B11") (pin "21") (pinfunction "O7_21") (pintype "bidirectional"))
      (node (ref "B7") (pin "4") (pinfunction "D2_4") (pintype "input"))
      (node (ref "B8") (pin "21") (pinfunction "O7_21") (pintype "bidirectional"))
      (node (ref "B9") (pin "21") (pinfunction "O7_21") (pintype "bidirectional"))
      (node (ref "ST") (pin "6") (pinfunction "6_6") (pintype "passive"))
    )
    (net (code "156") (name "NX4") (class "Default")
      (node (ref "B10") (pin "22") (pinfunction "O8_22") (pintype "bidirectional"))
      (node (ref "B11") (pin "22") (pinfunction "O8_22") (pintype "bidirectional"))
      (node (ref "B7") (pin "18") (pinfunction "D8_18") (pintype "input"))
      (node (ref "B8") (pin "22") (pinfunction "O8_22") (pintype "bidirectional"))
      (node (ref "B9") (pin "22") (pinfunction "O8_22") (pintype "bidirectional"))
      (node (ref "ST") (pin "4") (pinfunction "4_4") (pintype "passive"))
    )
    (net (code "157") (name "NX5") (class "Default")
      (node (ref "B10") (pin "23") (pinfunction "O9_23") (pintype "bidirectional"))
      (node (ref "B11") (pin "23") (pinfunction "O9_23") (pintype "bidirectional"))
      (node (ref "B7") (pin "3") (pinfunction "D1_3") (pintype "input"))
      (node (ref "B8") (pin "23") (pinfunction "O9_23") (pintype "bidirectional"))
      (node (ref "B9") (pin "23") (pinfunction "O9_23") (pintype "bidirectional"))
      (node (ref "ST") (pin "2") (pinfunction "2_2") (pintype "passive"))
    )
    (net (code "158") (name "Net-(A1A-QA)") (class "Default")
      (node (ref "A1") (pin "15") (pinfunction "QA_15") (pintype "output"))
      (node (ref "E2") (pin "2") (pinfunction "I1_2") (pintype "input"))
    )
    (net (code "159") (name "Net-(A1A-QB)") (class "Default")
      (node (ref "A1") (pin "14") (pinfunction "QB_14") (pintype "output"))
      (node (ref "E2") (pin "5") (pinfunction "I1_5") (pintype "input"))
    )
    (net (code "160") (name "Net-(A3A-J)") (class "Default")
      (node (ref "A3") (pin "2") (pinfunction "J_2") (pintype "input"))
      (node (ref "B4") (pin "20") (pinfunction "O6_20") (pintype "bidirectional"))
    )
    (net (code "161") (name "Net-(A3A-K)") (class "Default")
      (node (ref "A3") (pin "3") (pinfunction "K_3") (pintype "input"))
      (node (ref "B4") (pin "19") (pinfunction "O5_19") (pintype "bidirectional"))
    )
    (net (code "162") (name "Net-(C0A-TAP3)") (class "Default")
      (node (ref "C0") (pin "6") (pinfunction "TAP3_6") (pintype "output"))
      (node (ref "E0") (pin "9") (pinfunction "I0_9") (pintype "input"))
    )
    (net (code "163") (name "Net-(C4A-CN)") (class "Default")
      (node (ref "C4") (pin "7") (pinfunction "CN_7") (pintype "input"))
      (node (ref "C6") (pin "16") (pinfunction "CN+4_16") (pintype "output"))
    )
    (net (code "164") (name "Net-(C6A-CN)") (class "Default")
      (node (ref "C6") (pin "7") (pinfunction "CN_7") (pintype "input"))
      (node (ref "C9") (pin "16") (pinfunction "CN+4_16") (pintype "output"))
    )
    (net (code "165") (name "Net-(E0A-O)") (class "Default")
      (node (ref "E0") (pin "3") (pinfunction "O_3") (pintype "output"))
      (node (ref "E4") (pin "9") (pinfunction "I0_9") (pintype "input"))
    )
    (net (code "166") (name "Net-(E0B-O)") (class "Default")
      (node (ref "E0") (pin "6") (pinfunction "O_6") (pintype "output"))
      (node (ref "E4") (pin "11") (pinfunction "I2_11") (pintype "input"))
    )
    (net (code "167") (name "Net-(E3A-I1)") (class "Default")
      (node (ref "E3") (pin "2") (pinfunction "I1_2") (pintype "input"))
      (node (ref "E8") (pin "13") (pinfunction "W_13") (pintype "output"))
    )
    (net (code "168") (name "Net-(E3B-I1)") (class "Default")
      (node (ref "E3") (pin "5") (pinfunction "I1_5") (pintype "input"))
      (node (ref "E9") (pin "13") (pinfunction "W_13") (pintype "output"))
    )
    (net (code "169") (name "Net-(E4B-O)") (class "Default")
      (node (ref "E4") (pin "10") (pinfunction "I1_10") (pintype "input"))
      (node (ref "E4") (pin "6") (pinfunction "O_6") (pintype "output"))
    )
    (net (code "170") (name "Net-(E4C-O)") (class "Default")
      (node (ref "E4") (pin "8") (pinfunction "O_8") (pintype "output"))
      (node (ref "E6") (pin "9") (pinfunction "I0_9") (pintype "input"))
    )
    (net (code "171") (name "Net-(E10A-+UB)") (class "Default")
      (node (ref "E10") (pin "14") (pinfunction "+UB_14") (pintype "power_in"))
      (node (ref "E7") (pin "14") (pinfunction "+UB_14") (pintype "power_in"))
      (node (ref "E8") (pin "14") (pinfunction "+UB_14") (pintype "power_in"))
      (node (ref "E9") (pin "14") (pinfunction "+UB_14") (pintype "power_in"))
      (node (ref "J1") (pin "2") (pinfunction "2_2") (pintype "passive"))
    )
    (net (code "172") (name "Net-(E10B--UB)") (class "Default")
      (node (ref "E10") (pin "7") (pinfunction "-UB_7") (pintype "power_in"))
      (node (ref "E7") (pin "7") (pinfunction "-UB_7") (pintype "power_in"))
      (node (ref "E8") (pin "7") (pinfunction "-UB_7") (pintype "power_in"))
      (node (ref "E9") (pin "7") (pinfunction "-UB_7") (pintype "power_in"))
      (node (ref "J2") (pin "2") (pinfunction "2_2") (pintype "passive"))
    )
    (net (code "173") (name "Net-(E10C-W)") (class "Default")
      (node (ref "E10") (pin "13") (pinfunction "W_13") (pintype "output"))
      (node (ref "E4") (pin "5") (pinfunction "I2_5") (pintype "input"))
    )
    (net (code "174") (name "Net-(E11A-O)") (class "Default")
      (node (ref "E11") (pin "6") (pinfunction "O_6") (pintype "output"))
      (node (ref "E3") (pin "4") (pinfunction "I0_4") (pintype "input"))
    )
    (net (code "175") (name "Net-(E11B-O)") (class "Default")
      (node (ref "E11") (pin "8") (pinfunction "O_8") (pintype "output"))
      (node (ref "E4") (pin "4") (pinfunction "I1_4") (pintype "input"))
    )
    (net (code "176") (name "PC0") (class "Default")
      (node (ref "D0") (pin "18") (pinfunction "O4_18") (pintype "bidirectional"))
      (node (ref "PC") (pin "2") (pinfunction "2_2") (pintype "passive"))
    )
    (net (code "177") (name "PC1") (class "Default")
      (node (ref "D1") (pin "18") (pinfunction "O4_18") (pintype "bidirectional"))
      (node (ref "PC") (pin "4") (pinfunction "4_4") (pintype "passive"))
    )
    (net (code "178") (name "PC2") (class "Default")
      (node (ref "D2") (pin "18") (pinfunction "O4_18") (pintype "bidirectional"))
      (node (ref "PC") (pin "6") (pinfunction "6_6") (pintype "passive"))
    )
    (net (code "179") (name "PC3") (class "Default")
      (node (ref "D3") (pin "18") (pinfunction "O4_18") (pintype "bidirectional"))
      (node (ref "PC") (pin "8") (pinfunction "8_8") (pintype "passive"))
    )
    (net (code "180") (name "PC4") (class "Default")
      (node (ref "D4") (pin "18") (pinfunction "O4_18") (pintype "bidirectional"))
      (node (ref "PC") (pin "10") (pinfunction "10_10") (pintype "passive"))
    )
    (net (code "181") (name "PC5") (class "Default")
      (node (ref "D5") (pin "18") (pinfunction "O4_18") (pintype "bidirectional"))
      (node (ref "PC") (pin "12") (pinfunction "12_12") (pintype "passive"))
    )
    (net (code "182") (name "PC6") (class "Default")
      (node (ref "D6") (pin "18") (pinfunction "O4_18") (pintype "bidirectional"))
      (node (ref "PC") (pin "14") (pinfunction "14_14") (pintype "passive"))
    )
    (net (code "183") (name "PC7") (class "Default")
      (node (ref "D7") (pin "18") (pinfunction "O4_18") (pintype "bidirectional"))
      (node (ref "PC") (pin "16") (pinfunction "16_16") (pintype "passive"))
    )
    (net (code "184") (name "PC8") (class "Default")
      (node (ref "D8") (pin "18") (pinfunction "O4_18") (pintype "bidirectional"))
      (node (ref "PC") (pin "18") (pinfunction "18_18") (pintype "passive"))
    )
    (net (code "185") (name "PC9") (class "Default")
      (node (ref "D9") (pin "18") (pinfunction "O4_18") (pintype "bidirectional"))
      (node (ref "PC") (pin "20") (pinfunction "20_20") (pintype "passive"))
    )
    (net (code "186") (name "PC10") (class "Default")
      (node (ref "D10") (pin "18") (pinfunction "O4_18") (pintype "bidirectional"))
      (node (ref "PC") (pin "22") (pinfunction "22_22") (pintype "passive"))
    )
    (net (code "187") (name "PC11") (class "Default")
      (node (ref "D11") (pin "18") (pinfunction "O4_18") (pintype "bidirectional"))
      (node (ref "PC") (pin "24") (pinfunction "24_24") (pintype "passive"))
    )
    (net (code "188") (name "R0") (class "Default")
      (node (ref "B6") (pin "20") (pinfunction "O6_20") (pintype "bidirectional"))
      (node (ref "D0") (pin "5") (pinfunction "I3_5") (pintype "input"))
      (node (ref "D1") (pin "5") (pinfunction "I3_5") (pintype "input"))
      (node (ref "D10") (pin "5") (pinfunction "I3_5") (pintype "input"))
      (node (ref "D11") (pin "5") (pinfunction "I3_5") (pintype "input"))
      (node (ref "D2") (pin "5") (pinfunction "I3_5") (pintype "input"))
      (node (ref "D3") (pin "5") (pinfunction "I3_5") (pintype "input"))
      (node (ref "D4") (pin "5") (pinfunction "I3_5") (pintype "input"))
      (node (ref "D5") (pin "5") (pinfunction "I3_5") (pintype "input"))
      (node (ref "D6") (pin "5") (pinfunction "I3_5") (pintype "input"))
      (node (ref "D7") (pin "5") (pinfunction "I3_5") (pintype "input"))
      (node (ref "D8") (pin "5") (pinfunction "I3_5") (pintype "input"))
      (node (ref "D9") (pin "5") (pinfunction "I3_5") (pintype "input"))
      (node (ref "RXS") (pin "2") (pinfunction "2_2") (pintype "passive"))
    )
    (net (code "189") (name "R1") (class "Default")
      (node (ref "B6") (pin "21") (pinfunction "O7_21") (pintype "bidirectional"))
      (node (ref "D0") (pin "4") (pinfunction "I2_4") (pintype "input"))
      (node (ref "D1") (pin "4") (pinfunction "I2_4") (pintype "input"))
      (node (ref "D10") (pin "4") (pinfunction "I2_4") (pintype "input"))
      (node (ref "D11") (pin "4") (pinfunction "I2_4") (pintype "input"))
      (node (ref "D2") (pin "4") (pinfunction "I2_4") (pintype "input"))
      (node (ref "D3") (pin "4") (pinfunction "I2_4") (pintype "input"))
      (node (ref "D4") (pin "4") (pinfunction "I2_4") (pintype "input"))
      (node (ref "D5") (pin "4") (pinfunction "I2_4") (pintype "input"))
      (node (ref "D6") (pin "4") (pinfunction "I2_4") (pintype "input"))
      (node (ref "D7") (pin "4") (pinfunction "I2_4") (pintype "input"))
      (node (ref "D8") (pin "4") (pinfunction "I2_4") (pintype "input"))
      (node (ref "D9") (pin "4") (pinfunction "I2_4") (pintype "input"))
      (node (ref "RXS") (pin "4") (pinfunction "4_4") (pintype "passive"))
    )
    (net (code "190") (name "R2") (class "Default")
      (node (ref "B6") (pin "22") (pinfunction "O8_22") (pintype "bidirectional"))
      (node (ref "D0") (pin "3") (pinfunction "I1_3") (pintype "input"))
      (node (ref "D1") (pin "3") (pinfunction "I1_3") (pintype "input"))
      (node (ref "D10") (pin "3") (pinfunction "I1_3") (pintype "input"))
      (node (ref "D11") (pin "3") (pinfunction "I1_3") (pintype "input"))
      (node (ref "D2") (pin "3") (pinfunction "I1_3") (pintype "input"))
      (node (ref "D3") (pin "3") (pinfunction "I1_3") (pintype "input"))
      (node (ref "D4") (pin "3") (pinfunction "I1_3") (pintype "input"))
      (node (ref "D5") (pin "3") (pinfunction "I1_3") (pintype "input"))
      (node (ref "D6") (pin "3") (pinfunction "I1_3") (pintype "input"))
      (node (ref "D7") (pin "3") (pinfunction "I1_3") (pintype "input"))
      (node (ref "D8") (pin "3") (pinfunction "I1_3") (pintype "input"))
      (node (ref "D9") (pin "3") (pinfunction "I1_3") (pintype "input"))
      (node (ref "RXS") (pin "6") (pinfunction "6_6") (pintype "passive"))
    )
    (net (code "191") (name "R3") (class "Default")
      (node (ref "B6") (pin "23") (pinfunction "O9_23") (pintype "bidirectional"))
      (node (ref "D0") (pin "2") (pinfunction "I0_2") (pintype "input"))
      (node (ref "D1") (pin "2") (pinfunction "I0_2") (pintype "input"))
      (node (ref "D10") (pin "2") (pinfunction "I0_2") (pintype "input"))
      (node (ref "D11") (pin "2") (pinfunction "I0_2") (pintype "input"))
      (node (ref "D2") (pin "2") (pinfunction "I0_2") (pintype "input"))
      (node (ref "D3") (pin "2") (pinfunction "I0_2") (pintype "input"))
      (node (ref "D4") (pin "2") (pinfunction "I0_2") (pintype "input"))
      (node (ref "D5") (pin "2") (pinfunction "I0_2") (pintype "input"))
      (node (ref "D6") (pin "2") (pinfunction "I0_2") (pintype "input"))
      (node (ref "D7") (pin "2") (pinfunction "I0_2") (pintype "input"))
      (node (ref "D8") (pin "2") (pinfunction "I0_2") (pintype "input"))
      (node (ref "D9") (pin "2") (pinfunction "I0_2") (pintype "input"))
      (node (ref "RXS") (pin "8") (pinfunction "8_8") (pintype "passive"))
    )
    (net (code "192") (name "RESET*") (class "Default")
      (node (ref "E1") (pin "8") (pinfunction "I0_8") (pintype "input"))
      (node (ref "E1") (pin "9") (pinfunction "I1_9") (pintype "input"))
      (node (ref "FPCTL") (pin "10") (pinfunction "10_10") (pintype "passive"))
      (node (ref "R32") (pin "1") (pinfunction "1_1") (pintype "passive"))
    )
    (net (code "193") (name "RESET_L") (class "Default")
      (node (ref "A1") (pin "1") (pinfunction "CLR_1") (pintype "input"))
      (node (ref "A3") (pin "15") (pinfunction "CLR_15") (pintype "input"))
      (node (ref "A3") (pin "5") (pinfunction "PRE_5") (pintype "input"))
      (node (ref "B7") (pin "1") (pinfunction "CLR_1") (pintype "input"))
      (node (ref "E1") (pin "10") (pinfunction "O_10") (pintype "output"))
    )
    (net (code "194") (name "S0") (class "Default")
      (node (ref "B5") (pin "18") (pinfunction "O4_18") (pintype "bidirectional"))
      (node (ref "C4") (pin "6") (pinfunction "S0_6") (pintype "input"))
      (node (ref "C6") (pin "6") (pinfunction "S0_6") (pintype "input"))
      (node (ref "C9") (pin "6") (pinfunction "S0_6") (pintype "input"))
      (node (ref "RXS") (pin "16") (pinfunction "16_16") (pintype "passive"))
    )
    (net (code "195") (name "S1") (class "Default")
      (node (ref "B5") (pin "19") (pinfunction "O5_19") (pintype "bidirectional"))
      (node (ref "C4") (pin "5") (pinfunction "S1_5") (pintype "input"))
      (node (ref "C6") (pin "5") (pinfunction "S1_5") (pintype "input"))
      (node (ref "C9") (pin "5") (pinfunction "S1_5") (pintype "input"))
      (node (ref "RXS") (pin "18") (pinfunction "18_18") (pintype "passive"))
    )
    (net (code "196") (name "S3") (class "Default")
      (node (ref "B5") (pin "20") (pinfunction "O6_20") (pintype "bidirectional"))
      (node (ref "C4") (pin "3") (pinfunction "S3_3") (pintype "input"))
      (node (ref "C6") (pin "3") (pinfunction "S3_3") (pintype "input"))
      (node (ref "C9") (pin "3") (pinfunction "S3_3") (pintype "input"))
      (node (ref "RXS") (pin "22") (pinfunction "22_22") (pintype "passive"))
    )
    (net (code "197") (name "SHIFT") (class "Default")
      (node (ref "B9") (pin "11") (pinfunction "I9_11") (pintype "input"))
      (node (ref "E5") (pin "8") (pinfunction "O_8") (pintype "output"))
    )
    (net (code "198") (name "SINGLE*") (class "Default")
      (node (ref "B4") (pin "9") (pinfunction "I7_9") (pintype "input"))
      (node (ref "FPCTL") (pin "12") (pinfunction "12_12") (pintype "passive"))
      (node (ref "R33") (pin "1") (pinfunction "1_1") (pintype "passive"))
    )
    (net (code "199") (name "SKIP") (class "Default")
      (node (ref "B5") (pin "10") (pinfunction "I8_10") (pintype "input"))
      (node (ref "E6") (pin "8") (pinfunction "O_8") (pintype "output"))
    )
    (net (code "200") (name "SLIOP") (class "Default")
      (node (ref "A1") (pin "9") (pinfunction "S0_9") (pintype "input"))
      (node (ref "B4") (pin "16") (pinfunction "O2_16") (pintype "bidirectional"))
    )
    (net (code "201") (name "ST0") (class "Default")
      (node (ref "B4") (pin "7") (pinfunction "I5_7") (pintype "input"))
      (node (ref "B5") (pin "7") (pinfunction "I5_7") (pintype "input"))
      (node (ref "B6") (pin "7") (pinfunction "I5_7") (pintype "input"))
      (node (ref "B7") (pin "15") (pinfunction "Q6_15") (pintype "output"))
      (node (ref "B8") (pin "7") (pinfunction "I5_7") (pintype "input"))
      (node (ref "B9") (pin "7") (pinfunction "I5_7") (pintype "input"))
      (node (ref "ST") (pin "24") (pinfunction "24_24") (pintype "passive"))
    )
    (net (code "202") (name "ST1") (class "Default")
      (node (ref "B4") (pin "6") (pinfunction "I4_6") (pintype "input"))
      (node (ref "B5") (pin "6") (pinfunction "I4_6") (pintype "input"))
      (node (ref "B6") (pin "6") (pinfunction "I4_6") (pintype "input"))
      (node (ref "B7") (pin "6") (pinfunction "Q3_6") (pintype "output"))
      (node (ref "B8") (pin "6") (pinfunction "I4_6") (pintype "input"))
      (node (ref "B9") (pin "6") (pinfunction "I4_6") (pintype "input"))
      (node (ref "ST") (pin "22") (pinfunction "22_22") (pintype "passive"))
    )
    (net (code "203") (name "ST2") (class "Default")
      (node (ref "B4") (pin "5") (pinfunction "I3_5") (pintype "input"))
      (node (ref "B5") (pin "5") (pinfunction "I3_5") (pintype "input"))
      (node (ref "B6") (pin "5") (pinfunction "I3_5") (pintype "input"))
      (node (ref "B7") (pin "16") (pinfunction "Q7_16") (pintype "output"))
      (node (ref "B8") (pin "5") (pinfunction "I3_5") (pintype "input"))
      (node (ref "B9") (pin "5") (pinfunction "I3_5") (pintype "input"))
      (node (ref "ST") (pin "20") (pinfunction "20_20") (pintype "passive"))
    )
    (net (code "204") (name "ST3") (class "Default")
      (node (ref "B4") (pin "4") (pinfunction "I2_4") (pintype "input"))
      (node (ref "B5") (pin "4") (pinfunction "I2_4") (pintype "input"))
      (node (ref "B6") (pin "4") (pinfunction "I2_4") (pintype "input"))
      (node (ref "B7") (pin "5") (pinfunction "Q2_5") (pintype "output"))
      (node (ref "B8") (pin "4") (pinfunction "I2_4") (pintype "input"))
      (node (ref "B9") (pin "4") (pinfunction "I2_4") (pintype "input"))
      (node (ref "ST") (pin "18") (pinfunction "18_18") (pintype "passive"))
    )
    (net (code "205") (name "ST4") (class "Default")
      (node (ref "B4") (pin "3") (pinfunction "I1_3") (pintype "input"))
      (node (ref "B5") (pin "3") (pinfunction "I1_3") (pintype "input"))
      (node (ref "B6") (pin "3") (pinfunction "I1_3") (pintype "input"))
      (node (ref "B7") (pin "19") (pinfunction "Q8_19") (pintype "output"))
      (node (ref "B8") (pin "3") (pinfunction "I1_3") (pintype "input"))
      (node (ref "B9") (pin "3") (pinfunction "I1_3") (pintype "input"))
      (node (ref "ST") (pin "16") (pinfunction "16_16") (pintype "passive"))
    )
    (net (code "206") (name "ST5") (class "Default")
      (node (ref "B4") (pin "2") (pinfunction "I0_2") (pintype "input"))
      (node (ref "B5") (pin "2") (pinfunction "I0_2") (pintype "input"))
      (node (ref "B6") (pin "2") (pinfunction "I0_2") (pintype "input"))
      (node (ref "B7") (pin "2") (pinfunction "Q1_2") (pintype "output"))
      (node (ref "B8") (pin "2") (pinfunction "I0_2") (pintype "input"))
      (node (ref "B9") (pin "2") (pinfunction "I0_2") (pintype "input"))
      (node (ref "ST") (pin "14") (pinfunction "14_14") (pintype "passive"))
    )
    (net (code "207") (name "STD") (class "Default")
      (node (ref "B10") (pin "1") (pinfunction "CLK/I0_1") (pintype "input"))
      (node (ref "B9") (pin "16") (pinfunction "O2_16") (pintype "bidirectional"))
    )
    (net (code "208") (name "STIDLE") (class "Default")
      (node (ref "B11") (pin "1") (pinfunction "CLK/I0_1") (pintype "input"))
      (node (ref "B8") (pin "14") (pinfunction "O0_14") (pintype "bidirectional"))
    )
    (net (code "209") (name "STIOTX") (class "Default")
      (node (ref "B10") (pin "3") (pinfunction "I1_3") (pintype "input"))
      (node (ref "B9") (pin "17") (pinfunction "O3_17") (pintype "bidirectional"))
    )
    (net (code "210") (name "STN") (class "Default")
      (node (ref "B10") (pin "2") (pinfunction "I0_2") (pintype "input"))
      (node (ref "B9") (pin "15") (pinfunction "O1_15") (pintype "bidirectional"))
    )
    (net (code "211") (name "SW0") (class "Default")
      (node (ref "D0") (pin "15") (pinfunction "O1_15") (pintype "bidirectional"))
      (node (ref "R16") (pin "1") (pinfunction "1_1") (pintype "passive"))
      (node (ref "SW") (pin "2") (pinfunction "2_2") (pintype "passive"))
    )
    (net (code "212") (name "SW1") (class "Default")
      (node (ref "D1") (pin "15") (pinfunction "O1_15") (pintype "bidirectional"))
      (node (ref "R17") (pin "1") (pinfunction "1_1") (pintype "passive"))
      (node (ref "SW") (pin "4") (pinfunction "4_4") (pintype "passive"))
    )
    (net (code "213") (name "SW2") (class "Default")
      (node (ref "D2") (pin "15") (pinfunction "O1_15") (pintype "bidirectional"))
      (node (ref "R18") (pin "1") (pinfunction "1_1") (pintype "passive"))
      (node (ref "SW") (pin "6") (pinfunction "6_6") (pintype "passive"))
    )
    (net (code "214") (name "SW3") (class "Default")
      (node (ref "D3") (pin "15") (pinfunction "O1_15") (pintype "bidirectional"))
      (node (ref "R19") (pin "1") (pinfunction "1_1") (pintype "passive"))
      (node (ref "SW") (pin "8") (pinfunction "8_8") (pintype "passive"))
    )
    (net (code "215") (name "SW4") (class "Default")
      (node (ref "D4") (pin "15") (pinfunction "O1_15") (pintype "bidirectional"))
      (node (ref "R20") (pin "1") (pinfunction "1_1") (pintype "passive"))
      (node (ref "SW") (pin "10") (pinfunction "10_10") (pintype "passive"))
    )
    (net (code "216") (name "SW5") (class "Default")
      (node (ref "D5") (pin "15") (pinfunction "O1_15") (pintype "bidirectional"))
      (node (ref "R21") (pin "1") (pinfunction "1_1") (pintype "passive"))
      (node (ref "SW") (pin "12") (pinfunction "12_12") (pintype "passive"))
    )
    (net (code "217") (name "SW6") (class "Default")
      (node (ref "D6") (pin "15") (pinfunction "O1_15") (pintype "bidirectional"))
      (node (ref "R22") (pin "1") (pinfunction "1_1") (pintype "passive"))
      (node (ref "SW") (pin "14") (pinfunction "14_14") (pintype "passive"))
    )
    (net (code "218") (name "SW7") (class "Default")
      (node (ref "D7") (pin "15") (pinfunction "O1_15") (pintype "bidirectional"))
      (node (ref "R23") (pin "1") (pinfunction "1_1") (pintype "passive"))
      (node (ref "SW") (pin "16") (pinfunction "16_16") (pintype "passive"))
    )
    (net (code "219") (name "SW8") (class "Default")
      (node (ref "D8") (pin "15") (pinfunction "O1_15") (pintype "bidirectional"))
      (node (ref "R24") (pin "1") (pinfunction "1_1") (pintype "passive"))
      (node (ref "SW") (pin "18") (pinfunction "18_18") (pintype "passive"))
    )
    (net (code "220") (name "SW9") (class "Default")
      (node (ref "D9") (pin "15") (pinfunction "O1_15") (pintype "bidirectional"))
      (node (ref "R25") (pin "1") (pinfunction "1_1") (pintype "passive"))
      (node (ref "SW") (pin "20") (pinfunction "20_20") (pintype "passive"))
    )
    (net (code "221") (name "SW10") (class "Default")
      (node (ref "D10") (pin "15") (pinfunction "O1_15") (pintype "bidirectional"))
      (node (ref "R26") (pin "1") (pinfunction "1_1") (pintype "passive"))
      (node (ref "SW") (pin "22") (pinfunction "22_22") (pintype "passive"))
    )
    (net (code "222") (name "SW11") (class "Default")
      (node (ref "D11") (pin "15") (pinfunction "O1_15") (pintype "bidirectional"))
      (node (ref "R27") (pin "1") (pinfunction "1_1") (pintype "passive"))
      (node (ref "SW") (pin "24") (pinfunction "24_24") (pintype "passive"))
    )
    (net (code "223") (name "UCODE") (class "Default")
      (node (ref "B4") (pin "1") (pinfunction "CLK/I0_1") (pintype "input"))
      (node (ref "B5") (pin "1") (pinfunction "CLK/I0_1") (pintype "input"))
      (node (ref "B6") (pin "1") (pinfunction "CLK/I0_1") (pintype "input"))
      (node (ref "R1") (pin "2") (pinfunction "2_2") (pintype "passive"))
    )
    (net (code "224") (name "VCC") (class "Default")
      (node (ref "A0") (pin "1") (pinfunction "CLR_1") (pintype "input"))
      (node (ref "A1") (pin "3") (pinfunction "A_3") (pintype "input"))
      (node (ref "A3") (pin "1") (pinfunction "CLR_1") (pintype "input"))
      (node (ref "A3") (pin "11") (pinfunction "PRE_11") (pintype "input"))
      (node (ref "B8") (pin "1") (pinfunction "CLK/I0_1") (pintype "input"))
      (node (ref "B9") (pin "1") (pinfunction "CLK/I0_1") (pintype "input"))
      (node (ref "C10") (pin "1") (pinfunction "1_1") (pintype "passive"))
      (node (ref "C11") (pin "1") (pinfunction "1_1") (pintype "passive"))
      (node (ref "C12") (pin "1") (pinfunction "1_1") (pintype "passive"))
      (node (ref "C13") (pin "1") (pinfunction "1_1") (pintype "passive"))
      (node (ref "C14") (pin "1") (pinfunction "1_1") (pintype "passive"))
      (node (ref "C15") (pin "1") (pinfunction "1_1") (pintype "passive"))
      (node (ref "C16") (pin "1") (pinfunction "1_1") (pintype "passive"))
      (node (ref "C17") (pin "1") (pinfunction "1_1") (pintype "passive"))
      (node (ref "C18") (pin "1") (pinfunction "1_1") (pintype "passive"))
      (node (ref "C19") (pin "1") (pinfunction "1_1") (pintype "passive"))
      (node (ref "C20") (pin "1") (pinfunction "1_1") (pintype "passive"))
      (node (ref "C21") (pin "1") (pinfunction "1_1") (pintype "passive"))
      (node (ref "C22") (pin "1") (pinfunction "1_1") (pintype "passive"))
      (node (ref "C23") (pin "1") (pinfunction "1_1") (pintype "passive"))
      (node (ref "C24") (pin "1") (pinfunction "1_1") (pintype "passive"))
      (node (ref "C25") (pin "1") (pinfunction "1_1") (pintype "passive"))
      (node (ref "C26") (pin "1") (pinfunction "1_1") (pintype "passive"))
      (node (ref "C27") (pin "1") (pinfunction "1_1") (pintype "passive"))
      (node (ref "C28") (pin "1") (pinfunction "1_1") (pintype "passive"))
      (node (ref "C29") (pin "1") (pinfunction "1_1") (pintype "passive"))
      (node (ref "C30") (pin "1") (pinfunction "1_1") (pintype "passive"))
      (node (ref "C31") (pin "1") (pinfunction "1_1") (pintype "passive"))
      (node (ref "C32") (pin "1") (pinfunction "1_1") (pintype "passive"))
      (node (ref "C33") (pin "1") (pinfunction "1_1") (pintype "passive"))
      (node (ref "C34") (pin "1") (pinfunction "1_1") (pintype "passive"))
      (node (ref "C35") (pin "1") (pinfunction "1_1") (pintype "passive"))
      (node (ref "C36") (pin "1") (pinfunction "1_1") (pintype "passive"))
      (node (ref "C37") (pin "1") (pinfunction "1_1") (pintype "passive"))
      (node (ref "C38") (pin "1") (pinfunction "1_1") (pintype "passive"))
      (node (ref "C39") (pin "1") (pinfunction "1_1") (pintype "passive"))
      (node (ref "C40") (pin "1") (pinfunction "1_1") (pintype "passive"))
      (node (ref "C41") (pin "1") (pinfunction "1_1") (pintype "passive"))
      (node (ref "C42") (pin "1") (pinfunction "1_1") (pintype "passive"))
      (node (ref "C43") (pin "1") (pinfunction "1_1") (pintype "passive"))
      (node (ref "C44") (pin "1") (pinfunction "1_1") (pintype "passive"))
      (node (ref "C45") (pin "1") (pinfunction "1_1") (pintype "passive"))
      (node (ref "C46") (pin "1") (pinfunction "1_1") (pintype "passive"))
      (node (ref "C47") (pin "1") (pinfunction "1_1") (pintype "passive"))
      (node (ref "C48") (pin "1") (pinfunction "1_1") (pintype "passive"))
      (node (ref "C49") (pin "1") (pinfunction "1_1") (pintype "passive"))
      (node (ref "C50") (pin "1") (pinfunction "1_1") (pintype "passive"))
      (node (ref "C51") (pin "1") (pinfunction "1_1") (pintype "passive"))
      (node (ref "C52") (pin "1") (pinfunction "1_1") (pintype "passive"))
      (node (ref "E11") (pin "11") (pinfunction "G_11") (pintype "input"))
      (node (ref "E11") (pin "3") (pinfunction "G_3") (pintype "input"))
      (node (ref "J1") (pin "1") (pinfunction "1_1") (pintype "passive"))
      (node (ref "R1") (pin "1") (pinfunction "1_1") (pintype "passive"))
      (node (ref "R10") (pin "2") (pinfunction "2_2") (pintype "passive"))
      (node (ref "R11") (pin "2") (pinfunction "2_2") (pintype "passive"))
      (node (ref "R12") (pin "2") (pinfunction "2_2") (pintype "passive"))
      (node (ref "R13") (pin "2") (pinfunction "2_2") (pintype "passive"))
      (node (ref "R14") (pin "2") (pinfunction "2_2") (pintype "passive"))
      (node (ref "R15") (pin "2") (pinfunction "2_2") (pintype "passive"))
      (node (ref "R16") (pin "2") (pinfunction "2_2") (pintype "passive"))
      (node (ref "R17") (pin "2") (pinfunction "2_2") (pintype "passive"))
      (node (ref "R18") (pin "2") (pinfunction "2_2") (pintype "passive"))
      (node (ref "R19") (pin "2") (pinfunction "2_2") (pintype "passive"))
      (node (ref "R20") (pin "2") (pinfunction "2_2") (pintype "passive"))
      (node (ref "R21") (pin "2") (pinfunction "2_2") (pintype "passive"))
      (node (ref "R22") (pin "2") (pinfunction "2_2") (pintype "passive"))
      (node (ref "R23") (pin "2") (pinfunction "2_2") (pintype "passive"))
      (node (ref "R24") (pin "2") (pinfunction "2_2") (pintype "passive"))
      (node (ref "R25") (pin "2") (pinfunction "2_2") (pintype "passive"))
      (node (ref "R26") (pin "2") (pinfunction "2_2") (pintype "passive"))
      (node (ref "R27") (pin "2") (pinfunction "2_2") (pintype "passive"))
      (node (ref "R28") (pin "2") (pinfunction "2_2") (pintype "passive"))
      (node (ref "R29") (pin "2") (pinfunction "2_2") (pintype "passive"))
      (node (ref "R30") (pin "2") (pinfunction "2_2") (pintype "passive"))
      (node (ref "R31") (pin "2") (pinfunction "2_2") (pintype "passive"))
      (node (ref "R32") (pin "2") (pinfunction "2_2") (pintype "passive"))
      (node (ref "R33") (pin "2") (pinfunction "2_2") (pintype "passive"))
      (node (ref "R34") (pin "2") (pinfunction "2_2") (pintype "passive"))
      (node (ref "R35") (pin "2") (pinfunction "2_2") (pintype "passive"))
      (node (ref "R36") (pin "2") (pinfunction "2_2") (pintype "passive"))
      (node (ref "R37") (pin "2") (pinfunction "2_2") (pintype "passive"))
      (node (ref "R38") (pin "2") (pinfunction "2_2") (pintype "passive"))
      (node (ref "R39") (pin "2") (pinfunction "2_2") (pintype "passive"))
      (node (ref "R4") (pin "2") (pinfunction "2_2") (pintype "passive"))
      (node (ref "R40") (pin "2") (pinfunction "2_2") (pintype "passive"))
      (node (ref "R43") (pin "2") (pinfunction "2_2") (pintype "passive"))
      (node (ref "R44") (pin "2") (pinfunction "2_2") (pintype "passive"))
      (node (ref "R45") (pin "2") (pinfunction "2_2") (pintype "passive"))
      (node (ref "R46") (pin "2") (pinfunction "2_2") (pintype "passive"))
      (node (ref "R5") (pin "2") (pinfunction "2_2") (pintype "passive"))
      (node (ref "R6") (pin "2") (pinfunction "2_2") (pintype "passive"))
      (node (ref "R7") (pin "2") (pinfunction "2_2") (pintype "passive"))
      (node (ref "R8") (pin "2") (pinfunction "2_2") (pintype "passive"))
      (node (ref "R9") (pin "2") (pinfunction "2_2") (pintype "passive"))
    )
    (net (code "225") (name "WE_L") (class "Default")
      (node (ref "C1") (pin "11") (pinfunction "~{WE}_11") (pintype "input"))
      (node (ref "C2") (pin "11") (pinfunction "~{WE}_11") (pintype "input"))
      (node (ref "C3") (pin "11") (pinfunction "~{WE}_11") (pintype "input"))
      (node (ref "E0") (pin "8") (pinfunction "O_8") (pintype "output"))
    )
    (net (code "226") (name "WRITE") (class "Default")
      (node (ref "A0") (pin "15") (pinfunction "Q4_15") (pintype "output"))
      (node (ref "E0") (pin "10") (pinfunction "I1_10") (pintype "input"))
    )
    (net (code "227") (name "WRITE_L") (class "Default")
      (node (ref "A0") (pin "14") (pinfunction "~{Q4}_14") (pintype "output"))
      (node (ref "C0") (pin "1") (pinfunction "IN_1") (pintype "input"))
    )
    (net (code "228") (name "WR_ST") (class "Default")
      (node (ref "A0") (pin "13") (pinfunction "D4_13") (pintype "input"))
      (node (ref "B4") (pin "14") (pinfunction "O0_14") (pintype "bidirectional"))
    )
    (net (code "229") (name "X0") (class "Default")
      (node (ref "B5") (pin "21") (pinfunction "O7_21") (pintype "bidirectional"))
      (node (ref "D0") (pin "8") (pinfunction "I6_8") (pintype "input"))
      (node (ref "D1") (pin "8") (pinfunction "I6_8") (pintype "input"))
      (node (ref "D10") (pin "8") (pinfunction "I6_8") (pintype "input"))
      (node (ref "D11") (pin "8") (pinfunction "I6_8") (pintype "input"))
      (node (ref "D2") (pin "8") (pinfunction "I6_8") (pintype "input"))
      (node (ref "D3") (pin "8") (pinfunction "I6_8") (pintype "input"))
      (node (ref "D4") (pin "8") (pinfunction "I6_8") (pintype "input"))
      (node (ref "D5") (pin "8") (pinfunction "I6_8") (pintype "input"))
      (node (ref "D6") (pin "8") (pinfunction "I6_8") (pintype "input"))
      (node (ref "D7") (pin "8") (pinfunction "I6_8") (pintype "input"))
      (node (ref "D8") (pin "8") (pinfunction "I6_8") (pintype "input"))
      (node (ref "D9") (pin "8") (pinfunction "I6_8") (pintype "input"))
      (node (ref "RXS") (pin "10") (pinfunction "10_10") (pintype "passive"))
    )
    (net (code "230") (name "X1") (class "Default")
      (node (ref "B5") (pin "22") (pinfunction "O8_22") (pintype "bidirectional"))
      (node (ref "D0") (pin "7") (pinfunction "I5_7") (pintype "input"))
      (node (ref "D1") (pin "7") (pinfunction "I5_7") (pintype "input"))
      (node (ref "D10") (pin "7") (pinfunction "I5_7") (pintype "input"))
      (node (ref "D11") (pin "7") (pinfunction "I5_7") (pintype "input"))
      (node (ref "D2") (pin "7") (pinfunction "I5_7") (pintype "input"))
      (node (ref "D3") (pin "7") (pinfunction "I5_7") (pintype "input"))
      (node (ref "D4") (pin "7") (pinfunction "I5_7") (pintype "input"))
      (node (ref "D5") (pin "7") (pinfunction "I5_7") (pintype "input"))
      (node (ref "D6") (pin "7") (pinfunction "I5_7") (pintype "input"))
      (node (ref "D7") (pin "7") (pinfunction "I5_7") (pintype "input"))
      (node (ref "D8") (pin "7") (pinfunction "I5_7") (pintype "input"))
      (node (ref "D9") (pin "7") (pinfunction "I5_7") (pintype "input"))
      (node (ref "RXS") (pin "12") (pinfunction "12_12") (pintype "passive"))
    )
    (net (code "231") (name "X2") (class "Default")
      (node (ref "B5") (pin "23") (pinfunction "O9_23") (pintype "bidirectional"))
      (node (ref "D0") (pin "6") (pinfunction "I4_6") (pintype "input"))
      (node (ref "D1") (pin "6") (pinfunction "I4_6") (pintype "input"))
      (node (ref "D10") (pin "6") (pinfunction "I4_6") (pintype "input"))
      (node (ref "D11") (pin "6") (pinfunction "I4_6") (pintype "input"))
      (node (ref "D2") (pin "6") (pinfunction "I4_6") (pintype "input"))
      (node (ref "D3") (pin "6") (pinfunction "I4_6") (pintype "input"))
      (node (ref "D4") (pin "6") (pinfunction "I4_6") (pintype "input"))
      (node (ref "D5") (pin "6") (pinfunction "I4_6") (pintype "input"))
      (node (ref "D6") (pin "6") (pinfunction "I4_6") (pintype "input"))
      (node (ref "D7") (pin "6") (pinfunction "I4_6") (pintype "input"))
      (node (ref "D8") (pin "6") (pinfunction "I4_6") (pintype "input"))
      (node (ref "D9") (pin "6") (pinfunction "I4_6") (pintype "input"))
      (node (ref "RXS") (pin "14") (pinfunction "14_14") (pintype "passive"))
    )
    (net (code "232") (name "unconnected-(A0A-Q3-Pad10)") (class "Default")
      (node (ref "A0") (pin "10") (pinfunction "Q3_10") (pintype "output"))
    )
    (net (code "233") (name "unconnected-(A1A-QD-Pad12)") (class "Default")
      (node (ref "A1") (pin "12") (pinfunction "QD_12") (pintype "output"))
    )
    (net (code "234") (name "unconnected-(A2A-W-Pad6)") (class "Default")
      (node (ref "A2") (pin "6") (pinfunction "W_6") (pintype "output"))
    )
    (net (code "235") (name "unconnected-(A3A-~{Q}-Pad7)") (class "Default")
      (node (ref "A3") (pin "7") (pinfunction "~{Q}_7") (pintype "output"))
    )
    (net (code "236") (name "unconnected-(A3B-~{Q}-Pad9)") (class "Default")
      (node (ref "A3") (pin "9") (pinfunction "~{Q}_9") (pintype "output"))
    )
    (net (code "237") (name "unconnected-(B5A-O0-Pad14)") (class "Default")
      (node (ref "B5") (pin "14") (pinfunction "O0_14") (pintype "bidirectional"))
    )
    (net (code "238") (name "unconnected-(B5A-O1-Pad15)") (class "Default")
      (node (ref "B5") (pin "15") (pinfunction "O1_15") (pintype "bidirectional"))
    )
    (net (code "239") (name "unconnected-(B6A-O3-Pad17)") (class "Default")
      (node (ref "B6") (pin "17") (pinfunction "O3_17") (pintype "bidirectional"))
    )
    (net (code "240") (name "unconnected-(B6A-O4-Pad18)") (class "Default")
      (node (ref "B6") (pin "18") (pinfunction "O4_18") (pintype "bidirectional"))
    )
    (net (code "241") (name "unconnected-(B6A-O5-Pad19)") (class "Default")
      (node (ref "B6") (pin "19") (pinfunction "O5_19") (pintype "bidirectional"))
    )
    (net (code "242") (name "unconnected-(B9A-O0-Pad14)") (class "Default")
      (node (ref "B9") (pin "14") (pinfunction "O0_14") (pintype "bidirectional"))
    )
    (net (code "243") (name "unconnected-(B10A-O1-Pad15)") (class "Default")
      (node (ref "B10") (pin "15") (pinfunction "O1_15") (pintype "bidirectional"))
    )
    (net (code "244") (name "unconnected-(B10A-O2-Pad16)") (class "Default")
      (node (ref "B10") (pin "16") (pinfunction "O2_16") (pintype "bidirectional"))
    )
    (net (code "245") (name "unconnected-(B11A-O3-Pad17)") (class "Default")
      (node (ref "B11") (pin "17") (pinfunction "O3_17") (pintype "bidirectional"))
    )
    (net (code "246") (name "unconnected-(C0A-TAP1-Pad7)") (class "Default")
      (node (ref "C0") (pin "7") (pinfunction "TAP1_7") (pintype "output"))
    )
    (net (code "247") (name "unconnected-(C0A-TAP2-Pad2)") (class "Default")
      (node (ref "C0") (pin "2") (pinfunction "TAP2_2") (pintype "output"))
    )
    (net (code "248") (name "unconnected-(C0A-TAP4-Pad3)") (class "Default")
      (node (ref "C0") (pin "3") (pinfunction "TAP4_3") (pintype "output"))
    )
    (net (code "249") (name "unconnected-(C0A-TAP5-Pad5)") (class "Default")
      (node (ref "C0") (pin "5") (pinfunction "TAP5_5") (pintype "output"))
    )
    (net (code "250") (name "unconnected-(C4A-A=B-Pad14)") (class "Default")
      (node (ref "C4") (pin "14") (pinfunction "A=B_14") (pintype "output"))
    )
    (net (code "251") (name "unconnected-(C4A-G-Pad17)") (class "Default")
      (node (ref "C4") (pin "17") (pinfunction "G_17") (pintype "output"))
    )
    (net (code "252") (name "unconnected-(C4A-P-Pad15)") (class "Default")
      (node (ref "C4") (pin "15") (pinfunction "P_15") (pintype "output"))
    )
    (net (code "253") (name "unconnected-(C6A-A=B-Pad14)") (class "Default")
      (node (ref "C6") (pin "14") (pinfunction "A=B_14") (pintype "output"))
    )
    (net (code "254") (name "unconnected-(C6A-G-Pad17)") (class "Default")
      (node (ref "C6") (pin "17") (pinfunction "G_17") (pintype "output"))
    )
    (net (code "255") (name "unconnected-(C6A-P-Pad15)") (class "Default")
      (node (ref "C6") (pin "15") (pinfunction "P_15") (pintype "output"))
    )
    (net (code "256") (name "unconnected-(C9A-A=B-Pad14)") (class "Default")
      (node (ref "C9") (pin "14") (pinfunction "A=B_14") (pintype "output"))
    )
    (net (code "257") (name "unconnected-(C9A-G-Pad17)") (class "Default")
      (node (ref "C9") (pin "17") (pinfunction "G_17") (pintype "output"))
    )
    (net (code "258") (name "unconnected-(C9A-P-Pad15)") (class "Default")
      (node (ref "C9") (pin "15") (pinfunction "P_15") (pintype "output"))
    )
    (net (code "259") (name "unconnected-(D0A-O2-Pad16)") (class "Default")
      (node (ref "D0") (pin "16") (pinfunction "O2_16") (pintype "bidirectional"))
    )
    (net (code "260") (name "unconnected-(D1A-O2-Pad16)") (class "Default")
      (node (ref "D1") (pin "16") (pinfunction "O2_16") (pintype "bidirectional"))
    )
    (net (code "261") (name "unconnected-(D2A-O2-Pad16)") (class "Default")
      (node (ref "D2") (pin "16") (pinfunction "O2_16") (pintype "bidirectional"))
    )
    (net (code "262") (name "unconnected-(D3A-O2-Pad16)") (class "Default")
      (node (ref "D3") (pin "16") (pinfunction "O2_16") (pintype "bidirectional"))
    )
    (net (code "263") (name "unconnected-(D4A-O2-Pad16)") (class "Default")
      (node (ref "D4") (pin "16") (pinfunction "O2_16") (pintype "bidirectional"))
    )
    (net (code "264") (name "unconnected-(D5A-O2-Pad16)") (class "Default")
      (node (ref "D5") (pin "16") (pinfunction "O2_16") (pintype "bidirectional"))
    )
    (net (code "265") (name "unconnected-(D6A-O2-Pad16)") (class "Default")
      (node (ref "D6") (pin "16") (pinfunction "O2_16") (pintype "bidirectional"))
    )
    (net (code "266") (name "unconnected-(D7A-O2-Pad16)") (class "Default")
      (node (ref "D7") (pin "16") (pinfunction "O2_16") (pintype "bidirectional"))
    )
    (net (code "267") (name "unconnected-(D8A-O2-Pad16)") (class "Default")
      (node (ref "D8") (pin "16") (pinfunction "O2_16") (pintype "bidirectional"))
    )
    (net (code "268") (name "unconnected-(D9A-O2-Pad16)") (class "Default")
      (node (ref "D9") (pin "16") (pinfunction "O2_16") (pintype "bidirectional"))
    )
    (net (code "269") (name "unconnected-(D10A-O2-Pad16)") (class "Default")
      (node (ref "D10") (pin "16") (pinfunction "O2_16") (pintype "bidirectional"))
    )
    (net (code "270") (name "unconnected-(D11A-O2-Pad16)") (class "Default")
      (node (ref "D11") (pin "16") (pinfunction "O2_16") (pintype "bidirectional"))
    )
    (net (code "271") (name "unconnected-(E7C-Y-Pad1)") (class "Default")
      (node (ref "E7") (pin "1") (pinfunction "Y_1") (pintype "output"))
    )
    (net (code "272") (name "unconnected-(E8C-Y-Pad1)") (class "Default")
      (node (ref "E8") (pin "1") (pinfunction "Y_1") (pintype "output"))
    )
    (net (code "273") (name "unconnected-(E9C-Y-Pad1)") (class "Default")
      (node (ref "E9") (pin "1") (pinfunction "Y_1") (pintype "output"))
    )
    (net (code "274") (name "unconnected-(E10C-Y-Pad1)") (class "Default")
      (node (ref "E10") (pin "1") (pinfunction "Y_1") (pintype "output"))
    )
    (net (code "275") (name "unconnected-(IOCTL-Pad16)") (class "Default")
      (node (ref "IOCTL") (pin "16") (pinfunction "16_16") (pintype "passive"))
    )
    (net (code "276") (name "unconnected-(IOCTL-Pad18)") (class "Default")
      (node (ref "IOCTL") (pin "18") (pinfunction "18_18") (pintype "passive"))
    )
    (net (code "277") (name "unconnected-(IOCTL-Pad20)") (class "Default")
      (node (ref "IOCTL") (pin "20") (pinfunction "20_20") (pintype "passive"))
    )
  )
)
